# protoboard-63.net
KiCad netlist of a schematic drawn in EAGLE
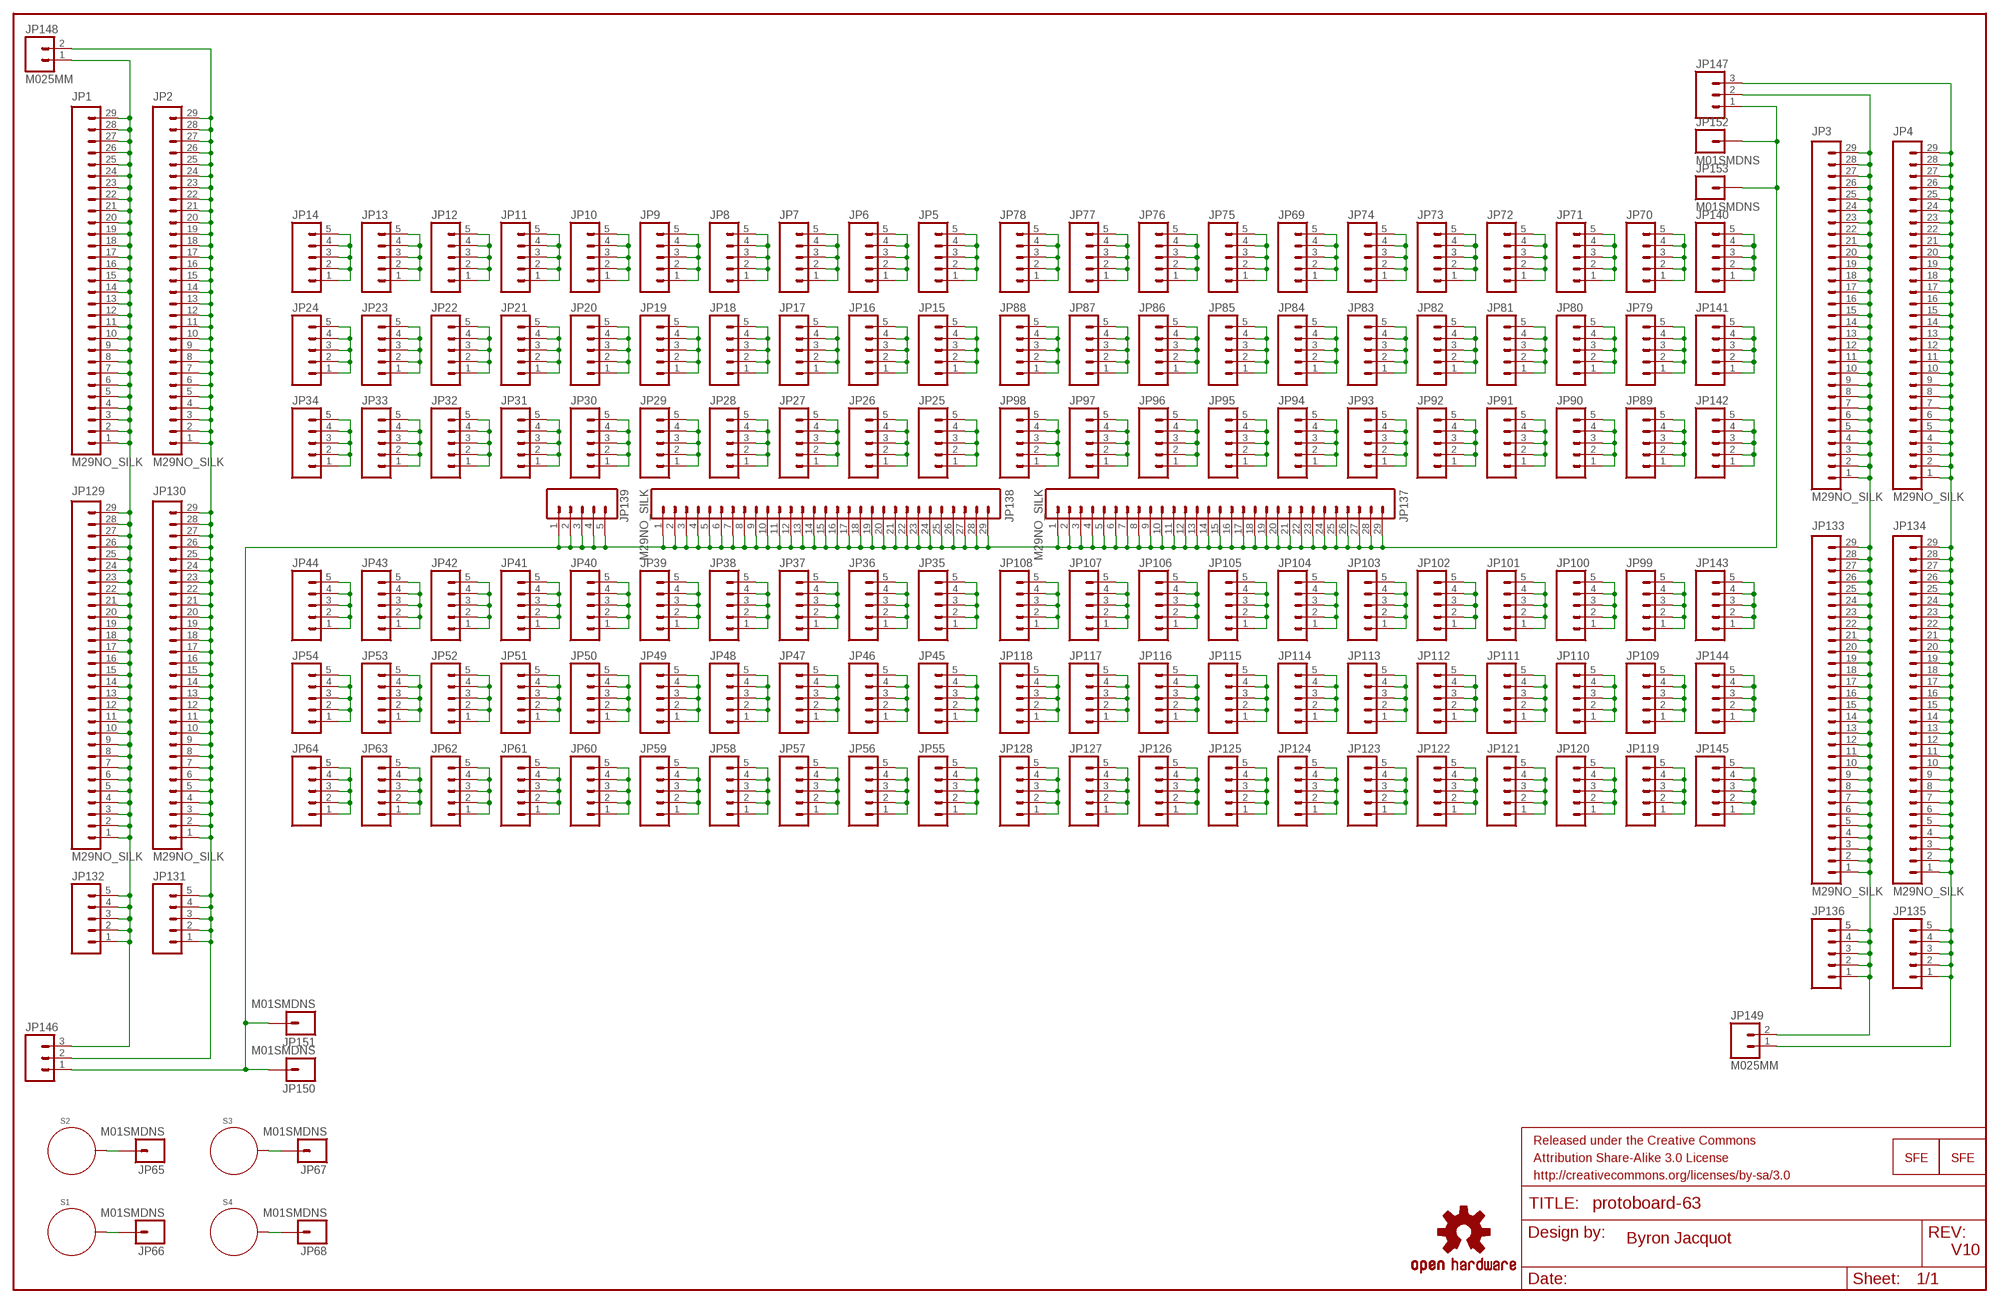
[diagram p0: schematic, sheet 1]

(export (version "E")
  (design (tool "Eeschema 10.0.6"))
  (components
    (comp (ref "FRAME2")
      (value "FRAME-LEDGER")
      (footprint "eagle-import:CREATIVE_COMMONS")
      (libsource (lib "eagle-import") (part "FRAME-LEDGER"))
    )
    (comp (ref "JP1")
      (value "M29NO_SILK")
      (footprint "eagle-import:1X29_NO_SILK")
      (libsource (lib "eagle-import") (part "M29NO_SILK"))
    )
    (comp (ref "JP2")
      (value "M29NO_SILK")
      (footprint "eagle-import:1X29_NO_SILK")
      (libsource (lib "eagle-import") (part "M29NO_SILK"))
    )
    (comp (ref "JP3")
      (value "M29NO_SILK")
      (footprint "eagle-import:1X29_NO_SILK")
      (libsource (lib "eagle-import") (part "M29NO_SILK"))
    )
    (comp (ref "JP4")
      (value "M29NO_SILK")
      (footprint "eagle-import:1X29_NO_SILK")
      (libsource (lib "eagle-import") (part "M29NO_SILK"))
    )
    (comp (ref "JP5")
      (value "M05NO_SILK")
      (footprint "eagle-import:1X05_NO_SILK")
      (libsource (lib "eagle-import") (part "M05NO_SILK"))
    )
    (comp (ref "JP6")
      (value "M05NO_SILK")
      (footprint "eagle-import:1X05_NO_SILK")
      (libsource (lib "eagle-import") (part "M05NO_SILK"))
    )
    (comp (ref "JP7")
      (value "M05NO_SILK")
      (footprint "eagle-import:1X05_NO_SILK")
      (libsource (lib "eagle-import") (part "M05NO_SILK"))
    )
    (comp (ref "JP8")
      (value "M05NO_SILK")
      (footprint "eagle-import:1X05_NO_SILK")
      (libsource (lib "eagle-import") (part "M05NO_SILK"))
    )
    (comp (ref "JP9")
      (value "M05NO_SILK")
      (footprint "eagle-import:1X05_NO_SILK")
      (libsource (lib "eagle-import") (part "M05NO_SILK"))
    )
    (comp (ref "JP10")
      (value "M05NO_SILK")
      (footprint "eagle-import:1X05_NO_SILK")
      (libsource (lib "eagle-import") (part "M05NO_SILK"))
    )
    (comp (ref "JP11")
      (value "M05NO_SILK")
      (footprint "eagle-import:1X05_NO_SILK")
      (libsource (lib "eagle-import") (part "M05NO_SILK"))
    )
    (comp (ref "JP12")
      (value "M05NO_SILK")
      (footprint "eagle-import:1X05_NO_SILK")
      (libsource (lib "eagle-import") (part "M05NO_SILK"))
    )
    (comp (ref "JP13")
      (value "M05NO_SILK")
      (footprint "eagle-import:1X05_NO_SILK")
      (libsource (lib "eagle-import") (part "M05NO_SILK"))
    )
    (comp (ref "JP14")
      (value "M05NO_SILK")
      (footprint "eagle-import:1X05_NO_SILK")
      (libsource (lib "eagle-import") (part "M05NO_SILK"))
    )
    (comp (ref "JP15")
      (value "M05NO_SILK")
      (footprint "eagle-import:1X05_NO_SILK")
      (libsource (lib "eagle-import") (part "M05NO_SILK"))
    )
    (comp (ref "JP16")
      (value "M05NO_SILK")
      (footprint "eagle-import:1X05_NO_SILK")
      (libsource (lib "eagle-import") (part "M05NO_SILK"))
    )
    (comp (ref "JP17")
      (value "M05NO_SILK")
      (footprint "eagle-import:1X05_NO_SILK")
      (libsource (lib "eagle-import") (part "M05NO_SILK"))
    )
    (comp (ref "JP18")
      (value "M05NO_SILK")
      (footprint "eagle-import:1X05_NO_SILK")
      (libsource (lib "eagle-import") (part "M05NO_SILK"))
    )
    (comp (ref "JP19")
      (value "M05NO_SILK")
      (footprint "eagle-import:1X05_NO_SILK")
      (libsource (lib "eagle-import") (part "M05NO_SILK"))
    )
    (comp (ref "JP20")
      (value "M05NO_SILK")
      (footprint "eagle-import:1X05_NO_SILK")
      (libsource (lib "eagle-import") (part "M05NO_SILK"))
    )
    (comp (ref "JP21")
      (value "M05NO_SILK")
      (footprint "eagle-import:1X05_NO_SILK")
      (libsource (lib "eagle-import") (part "M05NO_SILK"))
    )
    (comp (ref "JP22")
      (value "M05NO_SILK")
      (footprint "eagle-import:1X05_NO_SILK")
      (libsource (lib "eagle-import") (part "M05NO_SILK"))
    )
    (comp (ref "JP23")
      (value "M05NO_SILK")
      (footprint "eagle-import:1X05_NO_SILK")
      (libsource (lib "eagle-import") (part "M05NO_SILK"))
    )
    (comp (ref "JP24")
      (value "M05NO_SILK")
      (footprint "eagle-import:1X05_NO_SILK")
      (libsource (lib "eagle-import") (part "M05NO_SILK"))
    )
    (comp (ref "JP25")
      (value "M05NO_SILK")
      (footprint "eagle-import:1X05_NO_SILK")
      (libsource (lib "eagle-import") (part "M05NO_SILK"))
    )
    (comp (ref "JP26")
      (value "M05NO_SILK")
      (footprint "eagle-import:1X05_NO_SILK")
      (libsource (lib "eagle-import") (part "M05NO_SILK"))
    )
    (comp (ref "JP27")
      (value "M05NO_SILK")
      (footprint "eagle-import:1X05_NO_SILK")
      (libsource (lib "eagle-import") (part "M05NO_SILK"))
    )
    (comp (ref "JP28")
      (value "M05NO_SILK")
      (footprint "eagle-import:1X05_NO_SILK")
      (libsource (lib "eagle-import") (part "M05NO_SILK"))
    )
    (comp (ref "JP29")
      (value "M05NO_SILK")
      (footprint "eagle-import:1X05_NO_SILK")
      (libsource (lib "eagle-import") (part "M05NO_SILK"))
    )
    (comp (ref "JP30")
      (value "M05NO_SILK")
      (footprint "eagle-import:1X05_NO_SILK")
      (libsource (lib "eagle-import") (part "M05NO_SILK"))
    )
    (comp (ref "JP31")
      (value "M05NO_SILK")
      (footprint "eagle-import:1X05_NO_SILK")
      (libsource (lib "eagle-import") (part "M05NO_SILK"))
    )
    (comp (ref "JP32")
      (value "M05NO_SILK")
      (footprint "eagle-import:1X05_NO_SILK")
      (libsource (lib "eagle-import") (part "M05NO_SILK"))
    )
    (comp (ref "JP33")
      (value "M05NO_SILK")
      (footprint "eagle-import:1X05_NO_SILK")
      (libsource (lib "eagle-import") (part "M05NO_SILK"))
    )
    (comp (ref "JP34")
      (value "M05NO_SILK")
      (footprint "eagle-import:1X05_NO_SILK")
      (libsource (lib "eagle-import") (part "M05NO_SILK"))
    )
    (comp (ref "JP35")
      (value "M05NO_SILK")
      (footprint "eagle-import:1X05_NO_SILK")
      (libsource (lib "eagle-import") (part "M05NO_SILK"))
    )
    (comp (ref "JP36")
      (value "M05NO_SILK")
      (footprint "eagle-import:1X05_NO_SILK")
      (libsource (lib "eagle-import") (part "M05NO_SILK"))
    )
    (comp (ref "JP37")
      (value "M05NO_SILK")
      (footprint "eagle-import:1X05_NO_SILK")
      (libsource (lib "eagle-import") (part "M05NO_SILK"))
    )
    (comp (ref "JP38")
      (value "M05NO_SILK")
      (footprint "eagle-import:1X05_NO_SILK")
      (libsource (lib "eagle-import") (part "M05NO_SILK"))
    )
    (comp (ref "JP39")
      (value "M05NO_SILK")
      (footprint "eagle-import:1X05_NO_SILK")
      (libsource (lib "eagle-import") (part "M05NO_SILK"))
    )
    (comp (ref "JP40")
      (value "M05NO_SILK")
      (footprint "eagle-import:1X05_NO_SILK")
      (libsource (lib "eagle-import") (part "M05NO_SILK"))
    )
    (comp (ref "JP41")
      (value "M05NO_SILK")
      (footprint "eagle-import:1X05_NO_SILK")
      (libsource (lib "eagle-import") (part "M05NO_SILK"))
    )
    (comp (ref "JP42")
      (value "M05NO_SILK")
      (footprint "eagle-import:1X05_NO_SILK")
      (libsource (lib "eagle-import") (part "M05NO_SILK"))
    )
    (comp (ref "JP43")
      (value "M05NO_SILK")
      (footprint "eagle-import:1X05_NO_SILK")
      (libsource (lib "eagle-import") (part "M05NO_SILK"))
    )
    (comp (ref "JP44")
      (value "M05NO_SILK")
      (footprint "eagle-import:1X05_NO_SILK")
      (libsource (lib "eagle-import") (part "M05NO_SILK"))
    )
    (comp (ref "JP45")
      (value "M05NO_SILK")
      (footprint "eagle-import:1X05_NO_SILK")
      (libsource (lib "eagle-import") (part "M05NO_SILK"))
    )
    (comp (ref "JP46")
      (value "M05NO_SILK")
      (footprint "eagle-import:1X05_NO_SILK")
      (libsource (lib "eagle-import") (part "M05NO_SILK"))
    )
    (comp (ref "JP47")
      (value "M05NO_SILK")
      (footprint "eagle-import:1X05_NO_SILK")
      (libsource (lib "eagle-import") (part "M05NO_SILK"))
    )
    (comp (ref "JP48")
      (value "M05NO_SILK")
      (footprint "eagle-import:1X05_NO_SILK")
      (libsource (lib "eagle-import") (part "M05NO_SILK"))
    )
    (comp (ref "JP49")
      (value "M05NO_SILK")
      (footprint "eagle-import:1X05_NO_SILK")
      (libsource (lib "eagle-import") (part "M05NO_SILK"))
    )
    (comp (ref "JP50")
      (value "M05NO_SILK")
      (footprint "eagle-import:1X05_NO_SILK")
      (libsource (lib "eagle-import") (part "M05NO_SILK"))
    )
    (comp (ref "JP51")
      (value "M05NO_SILK")
      (footprint "eagle-import:1X05_NO_SILK")
      (libsource (lib "eagle-import") (part "M05NO_SILK"))
    )
    (comp (ref "JP52")
      (value "M05NO_SILK")
      (footprint "eagle-import:1X05_NO_SILK")
      (libsource (lib "eagle-import") (part "M05NO_SILK"))
    )
    (comp (ref "JP53")
      (value "M05NO_SILK")
      (footprint "eagle-import:1X05_NO_SILK")
      (libsource (lib "eagle-import") (part "M05NO_SILK"))
    )
    (comp (ref "JP54")
      (value "M05NO_SILK")
      (footprint "eagle-import:1X05_NO_SILK")
      (libsource (lib "eagle-import") (part "M05NO_SILK"))
    )
    (comp (ref "JP55")
      (value "M05NO_SILK")
      (footprint "eagle-import:1X05_NO_SILK")
      (libsource (lib "eagle-import") (part "M05NO_SILK"))
    )
    (comp (ref "JP56")
      (value "M05NO_SILK")
      (footprint "eagle-import:1X05_NO_SILK")
      (libsource (lib "eagle-import") (part "M05NO_SILK"))
    )
    (comp (ref "JP57")
      (value "M05NO_SILK")
      (footprint "eagle-import:1X05_NO_SILK")
      (libsource (lib "eagle-import") (part "M05NO_SILK"))
    )
    (comp (ref "JP58")
      (value "M05NO_SILK")
      (footprint "eagle-import:1X05_NO_SILK")
      (libsource (lib "eagle-import") (part "M05NO_SILK"))
    )
    (comp (ref "JP59")
      (value "M05NO_SILK")
      (footprint "eagle-import:1X05_NO_SILK")
      (libsource (lib "eagle-import") (part "M05NO_SILK"))
    )
    (comp (ref "JP60")
      (value "M05NO_SILK")
      (footprint "eagle-import:1X05_NO_SILK")
      (libsource (lib "eagle-import") (part "M05NO_SILK"))
    )
    (comp (ref "JP61")
      (value "M05NO_SILK")
      (footprint "eagle-import:1X05_NO_SILK")
      (libsource (lib "eagle-import") (part "M05NO_SILK"))
    )
    (comp (ref "JP62")
      (value "M05NO_SILK")
      (footprint "eagle-import:1X05_NO_SILK")
      (libsource (lib "eagle-import") (part "M05NO_SILK"))
    )
    (comp (ref "JP63")
      (value "M05NO_SILK")
      (footprint "eagle-import:1X05_NO_SILK")
      (libsource (lib "eagle-import") (part "M05NO_SILK"))
    )
    (comp (ref "JP64")
      (value "M05NO_SILK")
      (footprint "eagle-import:1X05_NO_SILK")
      (libsource (lib "eagle-import") (part "M05NO_SILK"))
    )
    (comp (ref "JP65")
      (value "M01SMDNS")
      (footprint "eagle-import:1X01NS")
      (libsource (lib "eagle-import") (part "M01SMDNS"))
    )
    (comp (ref "JP66")
      (value "M01SMDNS")
      (footprint "eagle-import:1X01NS")
      (libsource (lib "eagle-import") (part "M01SMDNS"))
    )
    (comp (ref "JP67")
      (value "M01SMDNS")
      (footprint "eagle-import:1X01NS")
      (libsource (lib "eagle-import") (part "M01SMDNS"))
    )
    (comp (ref "JP68")
      (value "M01SMDNS")
      (footprint "eagle-import:1X01NS")
      (libsource (lib "eagle-import") (part "M01SMDNS"))
    )
    (comp (ref "JP69")
      (value "M05NO_SILK")
      (footprint "eagle-import:1X05_NO_SILK")
      (libsource (lib "eagle-import") (part "M05NO_SILK"))
    )
    (comp (ref "JP70")
      (value "M05NO_SILK")
      (footprint "eagle-import:1X05_NO_SILK")
      (libsource (lib "eagle-import") (part "M05NO_SILK"))
    )
    (comp (ref "JP71")
      (value "M05NO_SILK")
      (footprint "eagle-import:1X05_NO_SILK")
      (libsource (lib "eagle-import") (part "M05NO_SILK"))
    )
    (comp (ref "JP72")
      (value "M05NO_SILK")
      (footprint "eagle-import:1X05_NO_SILK")
      (libsource (lib "eagle-import") (part "M05NO_SILK"))
    )
    (comp (ref "JP73")
      (value "M05NO_SILK")
      (footprint "eagle-import:1X05_NO_SILK")
      (libsource (lib "eagle-import") (part "M05NO_SILK"))
    )
    (comp (ref "JP74")
      (value "M05NO_SILK")
      (footprint "eagle-import:1X05_NO_SILK")
      (libsource (lib "eagle-import") (part "M05NO_SILK"))
    )
    (comp (ref "JP75")
      (value "M05NO_SILK")
      (footprint "eagle-import:1X05_NO_SILK")
      (libsource (lib "eagle-import") (part "M05NO_SILK"))
    )
    (comp (ref "JP76")
      (value "M05NO_SILK")
      (footprint "eagle-import:1X05_NO_SILK")
      (libsource (lib "eagle-import") (part "M05NO_SILK"))
    )
    (comp (ref "JP77")
      (value "M05NO_SILK")
      (footprint "eagle-import:1X05_NO_SILK")
      (libsource (lib "eagle-import") (part "M05NO_SILK"))
    )
    (comp (ref "JP78")
      (value "M05NO_SILK")
      (footprint "eagle-import:1X05_NO_SILK")
      (libsource (lib "eagle-import") (part "M05NO_SILK"))
    )
    (comp (ref "JP79")
      (value "M05NO_SILK")
      (footprint "eagle-import:1X05_NO_SILK")
      (libsource (lib "eagle-import") (part "M05NO_SILK"))
    )
    (comp (ref "JP80")
      (value "M05NO_SILK")
      (footprint "eagle-import:1X05_NO_SILK")
      (libsource (lib "eagle-import") (part "M05NO_SILK"))
    )
    (comp (ref "JP81")
      (value "M05NO_SILK")
      (footprint "eagle-import:1X05_NO_SILK")
      (libsource (lib "eagle-import") (part "M05NO_SILK"))
    )
    (comp (ref "JP82")
      (value "M05NO_SILK")
      (footprint "eagle-import:1X05_NO_SILK")
      (libsource (lib "eagle-import") (part "M05NO_SILK"))
    )
    (comp (ref "JP83")
      (value "M05NO_SILK")
      (footprint "eagle-import:1X05_NO_SILK")
      (libsource (lib "eagle-import") (part "M05NO_SILK"))
    )
    (comp (ref "JP84")
      (value "M05NO_SILK")
      (footprint "eagle-import:1X05_NO_SILK")
      (libsource (lib "eagle-import") (part "M05NO_SILK"))
    )
    (comp (ref "JP85")
      (value "M05NO_SILK")
      (footprint "eagle-import:1X05_NO_SILK")
      (libsource (lib "eagle-import") (part "M05NO_SILK"))
    )
    (comp (ref "JP86")
      (value "M05NO_SILK")
      (footprint "eagle-import:1X05_NO_SILK")
      (libsource (lib "eagle-import") (part "M05NO_SILK"))
    )
    (comp (ref "JP87")
      (value "M05NO_SILK")
      (footprint "eagle-import:1X05_NO_SILK")
      (libsource (lib "eagle-import") (part "M05NO_SILK"))
    )
    (comp (ref "JP88")
      (value "M05NO_SILK")
      (footprint "eagle-import:1X05_NO_SILK")
      (libsource (lib "eagle-import") (part "M05NO_SILK"))
    )
    (comp (ref "JP89")
      (value "M05NO_SILK")
      (footprint "eagle-import:1X05_NO_SILK")
      (libsource (lib "eagle-import") (part "M05NO_SILK"))
    )
    (comp (ref "JP90")
      (value "M05NO_SILK")
      (footprint "eagle-import:1X05_NO_SILK")
      (libsource (lib "eagle-import") (part "M05NO_SILK"))
    )
    (comp (ref "JP91")
      (value "M05NO_SILK")
      (footprint "eagle-import:1X05_NO_SILK")
      (libsource (lib "eagle-import") (part "M05NO_SILK"))
    )
    (comp (ref "JP92")
      (value "M05NO_SILK")
      (footprint "eagle-import:1X05_NO_SILK")
      (libsource (lib "eagle-import") (part "M05NO_SILK"))
    )
    (comp (ref "JP93")
      (value "M05NO_SILK")
      (footprint "eagle-import:1X05_NO_SILK")
      (libsource (lib "eagle-import") (part "M05NO_SILK"))
    )
    (comp (ref "JP94")
      (value "M05NO_SILK")
      (footprint "eagle-import:1X05_NO_SILK")
      (libsource (lib "eagle-import") (part "M05NO_SILK"))
    )
    (comp (ref "JP95")
      (value "M05NO_SILK")
      (footprint "eagle-import:1X05_NO_SILK")
      (libsource (lib "eagle-import") (part "M05NO_SILK"))
    )
    (comp (ref "JP96")
      (value "M05NO_SILK")
      (footprint "eagle-import:1X05_NO_SILK")
      (libsource (lib "eagle-import") (part "M05NO_SILK"))
    )
    (comp (ref "JP97")
      (value "M05NO_SILK")
      (footprint "eagle-import:1X05_NO_SILK")
      (libsource (lib "eagle-import") (part "M05NO_SILK"))
    )
    (comp (ref "JP98")
      (value "M05NO_SILK")
      (footprint "eagle-import:1X05_NO_SILK")
      (libsource (lib "eagle-import") (part "M05NO_SILK"))
    )
    (comp (ref "JP99")
      (value "M05NO_SILK")
      (footprint "eagle-import:1X05_NO_SILK")
      (libsource (lib "eagle-import") (part "M05NO_SILK"))
    )
    (comp (ref "JP100")
      (value "M05NO_SILK")
      (footprint "eagle-import:1X05_NO_SILK")
      (libsource (lib "eagle-import") (part "M05NO_SILK"))
    )
    (comp (ref "JP101")
      (value "M05NO_SILK")
      (footprint "eagle-import:1X05_NO_SILK")
      (libsource (lib "eagle-import") (part "M05NO_SILK"))
    )
    (comp (ref "JP102")
      (value "M05NO_SILK")
      (footprint "eagle-import:1X05_NO_SILK")
      (libsource (lib "eagle-import") (part "M05NO_SILK"))
    )
    (comp (ref "JP103")
      (value "M05NO_SILK")
      (footprint "eagle-import:1X05_NO_SILK")
      (libsource (lib "eagle-import") (part "M05NO_SILK"))
    )
    (comp (ref "JP104")
      (value "M05NO_SILK")
      (footprint "eagle-import:1X05_NO_SILK")
      (libsource (lib "eagle-import") (part "M05NO_SILK"))
    )
    (comp (ref "JP105")
      (value "M05NO_SILK")
      (footprint "eagle-import:1X05_NO_SILK")
      (libsource (lib "eagle-import") (part "M05NO_SILK"))
    )
    (comp (ref "JP106")
      (value "M05NO_SILK")
      (footprint "eagle-import:1X05_NO_SILK")
      (libsource (lib "eagle-import") (part "M05NO_SILK"))
    )
    (comp (ref "JP107")
      (value "M05NO_SILK")
      (footprint "eagle-import:1X05_NO_SILK")
      (libsource (lib "eagle-import") (part "M05NO_SILK"))
    )
    (comp (ref "JP108")
      (value "M05NO_SILK")
      (footprint "eagle-import:1X05_NO_SILK")
      (libsource (lib "eagle-import") (part "M05NO_SILK"))
    )
    (comp (ref "JP109")
      (value "M05NO_SILK")
      (footprint "eagle-import:1X05_NO_SILK")
      (libsource (lib "eagle-import") (part "M05NO_SILK"))
    )
    (comp (ref "JP110")
      (value "M05NO_SILK")
      (footprint "eagle-import:1X05_NO_SILK")
      (libsource (lib "eagle-import") (part "M05NO_SILK"))
    )
    (comp (ref "JP111")
      (value "M05NO_SILK")
      (footprint "eagle-import:1X05_NO_SILK")
      (libsource (lib "eagle-import") (part "M05NO_SILK"))
    )
    (comp (ref "JP112")
      (value "M05NO_SILK")
      (footprint "eagle-import:1X05_NO_SILK")
      (libsource (lib "eagle-import") (part "M05NO_SILK"))
    )
    (comp (ref "JP113")
      (value "M05NO_SILK")
      (footprint "eagle-import:1X05_NO_SILK")
      (libsource (lib "eagle-import") (part "M05NO_SILK"))
    )
    (comp (ref "JP114")
      (value "M05NO_SILK")
      (footprint "eagle-import:1X05_NO_SILK")
      (libsource (lib "eagle-import") (part "M05NO_SILK"))
    )
    (comp (ref "JP115")
      (value "M05NO_SILK")
      (footprint "eagle-import:1X05_NO_SILK")
      (libsource (lib "eagle-import") (part "M05NO_SILK"))
    )
    (comp (ref "JP116")
      (value "M05NO_SILK")
      (footprint "eagle-import:1X05_NO_SILK")
      (libsource (lib "eagle-import") (part "M05NO_SILK"))
    )
    (comp (ref "JP117")
      (value "M05NO_SILK")
      (footprint "eagle-import:1X05_NO_SILK")
      (libsource (lib "eagle-import") (part "M05NO_SILK"))
    )
    (comp (ref "JP118")
      (value "M05NO_SILK")
      (footprint "eagle-import:1X05_NO_SILK")
      (libsource (lib "eagle-import") (part "M05NO_SILK"))
    )
    (comp (ref "JP119")
      (value "M05NO_SILK")
      (footprint "eagle-import:1X05_NO_SILK")
      (libsource (lib "eagle-import") (part "M05NO_SILK"))
    )
    (comp (ref "JP120")
      (value "M05NO_SILK")
      (footprint "eagle-import:1X05_NO_SILK")
      (libsource (lib "eagle-import") (part "M05NO_SILK"))
    )
    (comp (ref "JP121")
      (value "M05NO_SILK")
      (footprint "eagle-import:1X05_NO_SILK")
      (libsource (lib "eagle-import") (part "M05NO_SILK"))
    )
    (comp (ref "JP122")
      (value "M05NO_SILK")
      (footprint "eagle-import:1X05_NO_SILK")
      (libsource (lib "eagle-import") (part "M05NO_SILK"))
    )
    (comp (ref "JP123")
      (value "M05NO_SILK")
      (footprint "eagle-import:1X05_NO_SILK")
      (libsource (lib "eagle-import") (part "M05NO_SILK"))
    )
    (comp (ref "JP124")
      (value "M05NO_SILK")
      (footprint "eagle-import:1X05_NO_SILK")
      (libsource (lib "eagle-import") (part "M05NO_SILK"))
    )
    (comp (ref "JP125")
      (value "M05NO_SILK")
      (footprint "eagle-import:1X05_NO_SILK")
      (libsource (lib "eagle-import") (part "M05NO_SILK"))
    )
    (comp (ref "JP126")
      (value "M05NO_SILK")
      (footprint "eagle-import:1X05_NO_SILK")
      (libsource (lib "eagle-import") (part "M05NO_SILK"))
    )
    (comp (ref "JP127")
      (value "M05NO_SILK")
      (footprint "eagle-import:1X05_NO_SILK")
      (libsource (lib "eagle-import") (part "M05NO_SILK"))
    )
    (comp (ref "JP128")
      (value "M05NO_SILK")
      (footprint "eagle-import:1X05_NO_SILK")
      (libsource (lib "eagle-import") (part "M05NO_SILK"))
    )
    (comp (ref "JP129")
      (value "M29NO_SILK")
      (footprint "eagle-import:1X29_NO_SILK")
      (libsource (lib "eagle-import") (part "M29NO_SILK"))
    )
    (comp (ref "JP130")
      (value "M29NO_SILK")
      (footprint "eagle-import:1X29_NO_SILK")
      (libsource (lib "eagle-import") (part "M29NO_SILK"))
    )
    (comp (ref "JP131")
      (value "M05NO_SILK")
      (footprint "eagle-import:1X05_NO_SILK")
      (libsource (lib "eagle-import") (part "M05NO_SILK"))
    )
    (comp (ref "JP132")
      (value "M05NO_SILK")
      (footprint "eagle-import:1X05_NO_SILK")
      (libsource (lib "eagle-import") (part "M05NO_SILK"))
    )
    (comp (ref "JP133")
      (value "M29NO_SILK")
      (footprint "eagle-import:1X29_NO_SILK")
      (libsource (lib "eagle-import") (part "M29NO_SILK"))
    )
    (comp (ref "JP134")
      (value "M29NO_SILK")
      (footprint "eagle-import:1X29_NO_SILK")
      (libsource (lib "eagle-import") (part "M29NO_SILK"))
    )
    (comp (ref "JP135")
      (value "M05NO_SILK")
      (footprint "eagle-import:1X05_NO_SILK")
      (libsource (lib "eagle-import") (part "M05NO_SILK"))
    )
    (comp (ref "JP136")
      (value "M05NO_SILK")
      (footprint "eagle-import:1X05_NO_SILK")
      (libsource (lib "eagle-import") (part "M05NO_SILK"))
    )
    (comp (ref "JP137")
      (value "M29NO_SILK")
      (footprint "eagle-import:1X29_NO_SILK")
      (libsource (lib "eagle-import") (part "M29NO_SILK"))
    )
    (comp (ref "JP138")
      (value "M29NO_SILK")
      (footprint "eagle-import:1X29_NO_SILK")
      (libsource (lib "eagle-import") (part "M29NO_SILK"))
    )
    (comp (ref "JP139")
      (value "M05NO_SILK")
      (footprint "eagle-import:1X05_NO_SILK")
      (libsource (lib "eagle-import") (part "M05NO_SILK"))
    )
    (comp (ref "JP140")
      (value "M05NO_SILK")
      (footprint "eagle-import:1X05_NO_SILK")
      (libsource (lib "eagle-import") (part "M05NO_SILK"))
    )
    (comp (ref "JP141")
      (value "M05NO_SILK")
      (footprint "eagle-import:1X05_NO_SILK")
      (libsource (lib "eagle-import") (part "M05NO_SILK"))
    )
    (comp (ref "JP142")
      (value "M05NO_SILK")
      (footprint "eagle-import:1X05_NO_SILK")
      (libsource (lib "eagle-import") (part "M05NO_SILK"))
    )
    (comp (ref "JP143")
      (value "M05NO_SILK")
      (footprint "eagle-import:1X05_NO_SILK")
      (libsource (lib "eagle-import") (part "M05NO_SILK"))
    )
    (comp (ref "JP144")
      (value "M05NO_SILK")
      (footprint "eagle-import:1X05_NO_SILK")
      (libsource (lib "eagle-import") (part "M05NO_SILK"))
    )
    (comp (ref "JP145")
      (value "M05NO_SILK")
      (footprint "eagle-import:1X05_NO_SILK")
      (libsource (lib "eagle-import") (part "M05NO_SILK"))
    )
    (comp (ref "JP146")
      (value "M03-SCREW-5MM")
      (footprint "eagle-import:SCREWTERMINAL-5MM-3")
      (libsource (lib "eagle-import") (part "M03-SCREW-5MM"))
    )
    (comp (ref "JP147")
      (value "M03-SCREW-5MM")
      (footprint "eagle-import:SCREWTERMINAL-5MM-3")
      (libsource (lib "eagle-import") (part "M03-SCREW-5MM"))
    )
    (comp (ref "JP148")
      (value "M025MM")
      (footprint "eagle-import:SCREWTERMINAL-5MM-2")
      (libsource (lib "eagle-import") (part "M025MM"))
    )
    (comp (ref "JP149")
      (value "M025MM")
      (footprint "eagle-import:SCREWTERMINAL-5MM-2")
      (libsource (lib "eagle-import") (part "M025MM"))
    )
    (comp (ref "JP150")
      (value "M01SMDNS")
      (footprint "eagle-import:1X01NS")
      (libsource (lib "eagle-import") (part "M01SMDNS"))
    )
    (comp (ref "JP151")
      (value "M01SMDNS")
      (footprint "eagle-import:1X01NS")
      (libsource (lib "eagle-import") (part "M01SMDNS"))
    )
    (comp (ref "JP152")
      (value "M01SMDNS")
      (footprint "eagle-import:1X01NS")
      (libsource (lib "eagle-import") (part "M01SMDNS"))
    )
    (comp (ref "JP153")
      (value "M01SMDNS")
      (footprint "eagle-import:1X01NS")
      (libsource (lib "eagle-import") (part "M01SMDNS"))
    )
    (comp (ref "LOGO1")
      (value "LOGO-SFENEW")
      (footprint "eagle-import:SFE-NEW-WEBLOGO")
      (libsource (lib "eagle-import") (part "LOGO-SFENEW"))
    )
    (comp (ref "LOGO2")
      (value "LOGO-SFENEW")
      (footprint "eagle-import:SFE-NEW-WEBLOGO")
      (libsource (lib "eagle-import") (part "LOGO-SFENEW"))
    )
    (comp (ref "LOGO3")
      (value "OSHW-LOGOS")
      (footprint "eagle-import:OSHW-LOGO-S")
      (libsource (lib "eagle-import") (part "OSHW-LOGOS"))
    )
    (comp (ref "S1")
      (value "STANDOFF_ELECTRICAL")
      (footprint "eagle-import:STANDOFF-ELECTRICAL")
      (libsource (lib "eagle-import") (part "STANDOFF_ELECTRICAL"))
    )
    (comp (ref "S2")
      (value "STANDOFF_ELECTRICAL")
      (footprint "eagle-import:STANDOFF-ELECTRICAL")
      (libsource (lib "eagle-import") (part "STANDOFF_ELECTRICAL"))
    )
    (comp (ref "S3")
      (value "STANDOFF_ELECTRICAL")
      (footprint "eagle-import:STANDOFF-ELECTRICAL")
      (libsource (lib "eagle-import") (part "STANDOFF_ELECTRICAL"))
    )
    (comp (ref "S4")
      (value "STANDOFF_ELECTRICAL")
      (footprint "eagle-import:STANDOFF-ELECTRICAL")
      (libsource (lib "eagle-import") (part "STANDOFF_ELECTRICAL"))
    )
  )
  (nets
    (net (code "1") (name "Net-(JP1-Pad1)") (class "Default")
      (node (ref "JP1") (pin "1") (pinfunction "1_1") (pintype "passive"))
      (node (ref "JP1") (pin "10") (pinfunction "10_10") (pintype "passive"))
      (node (ref "JP1") (pin "11") (pinfunction "11_11") (pintype "passive"))
      (node (ref "JP1") (pin "12") (pinfunction "12_12") (pintype "passive"))
      (node (ref "JP1") (pin "13") (pinfunction "13_13") (pintype "passive"))
      (node (ref "JP1") (pin "14") (pinfunction "14_14") (pintype "passive"))
      (node (ref "JP1") (pin "15") (pinfunction "15_15") (pintype "passive"))
      (node (ref "JP1") (pin "16") (pinfunction "16_16") (pintype "passive"))
      (node (ref "JP1") (pin "17") (pinfunction "17_17") (pintype "passive"))
      (node (ref "JP1") (pin "18") (pinfunction "18_18") (pintype "passive"))
      (node (ref "JP1") (pin "19") (pinfunction "19_19") (pintype "passive"))
      (node (ref "JP1") (pin "2") (pinfunction "2_2") (pintype "passive"))
      (node (ref "JP1") (pin "20") (pinfunction "20_20") (pintype "passive"))
      (node (ref "JP1") (pin "21") (pinfunction "21_21") (pintype "passive"))
      (node (ref "JP1") (pin "22") (pinfunction "22_22") (pintype "passive"))
      (node (ref "JP1") (pin "23") (pinfunction "23_23") (pintype "passive"))
      (node (ref "JP1") (pin "24") (pinfunction "24_24") (pintype "passive"))
      (node (ref "JP1") (pin "25") (pinfunction "25_25") (pintype "passive"))
      (node (ref "JP1") (pin "26") (pinfunction "26_26") (pintype "passive"))
      (node (ref "JP1") (pin "27") (pinfunction "27_27") (pintype "passive"))
      (node (ref "JP1") (pin "28") (pinfunction "28_28") (pintype "passive"))
      (node (ref "JP1") (pin "29") (pinfunction "29_29") (pintype "passive"))
      (node (ref "JP1") (pin "3") (pinfunction "3_3") (pintype "passive"))
      (node (ref "JP1") (pin "4") (pinfunction "4_4") (pintype "passive"))
      (node (ref "JP1") (pin "5") (pinfunction "5_5") (pintype "passive"))
      (node (ref "JP1") (pin "6") (pinfunction "6_6") (pintype "passive"))
      (node (ref "JP1") (pin "7") (pinfunction "7_7") (pintype "passive"))
      (node (ref "JP1") (pin "8") (pinfunction "8_8") (pintype "passive"))
      (node (ref "JP1") (pin "9") (pinfunction "9_9") (pintype "passive"))
      (node (ref "JP129") (pin "1") (pinfunction "1_1") (pintype "passive"))
      (node (ref "JP129") (pin "10") (pinfunction "10_10") (pintype "passive"))
      (node (ref "JP129") (pin "11") (pinfunction "11_11") (pintype "passive"))
      (node (ref "JP129") (pin "12") (pinfunction "12_12") (pintype "passive"))
      (node (ref "JP129") (pin "13") (pinfunction "13_13") (pintype "passive"))
      (node (ref "JP129") (pin "14") (pinfunction "14_14") (pintype "passive"))
      (node (ref "JP129") (pin "15") (pinfunction "15_15") (pintype "passive"))
      (node (ref "JP129") (pin "16") (pinfunction "16_16") (pintype "passive"))
      (node (ref "JP129") (pin "17") (pinfunction "17_17") (pintype "passive"))
      (node (ref "JP129") (pin "18") (pinfunction "18_18") (pintype "passive"))
      (node (ref "JP129") (pin "19") (pinfunction "19_19") (pintype "passive"))
      (node (ref "JP129") (pin "2") (pinfunction "2_2") (pintype "passive"))
      (node (ref "JP129") (pin "20") (pinfunction "20_20") (pintype "passive"))
      (node (ref "JP129") (pin "21") (pinfunction "21_21") (pintype "passive"))
      (node (ref "JP129") (pin "22") (pinfunction "22_22") (pintype "passive"))
      (node (ref "JP129") (pin "23") (pinfunction "23_23") (pintype "passive"))
      (node (ref "JP129") (pin "24") (pinfunction "24_24") (pintype "passive"))
      (node (ref "JP129") (pin "25") (pinfunction "25_25") (pintype "passive"))
      (node (ref "JP129") (pin "26") (pinfunction "26_26") (pintype "passive"))
      (node (ref "JP129") (pin "27") (pinfunction "27_27") (pintype "passive"))
      (node (ref "JP129") (pin "28") (pinfunction "28_28") (pintype "passive"))
      (node (ref "JP129") (pin "29") (pinfunction "29_29") (pintype "passive"))
      (node (ref "JP129") (pin "3") (pinfunction "3_3") (pintype "passive"))
      (node (ref "JP129") (pin "4") (pinfunction "4_4") (pintype "passive"))
      (node (ref "JP129") (pin "5") (pinfunction "5_5") (pintype "passive"))
      (node (ref "JP129") (pin "6") (pinfunction "6_6") (pintype "passive"))
      (node (ref "JP129") (pin "7") (pinfunction "7_7") (pintype "passive"))
      (node (ref "JP129") (pin "8") (pinfunction "8_8") (pintype "passive"))
      (node (ref "JP129") (pin "9") (pinfunction "9_9") (pintype "passive"))
      (node (ref "JP132") (pin "1") (pinfunction "1_1") (pintype "passive"))
      (node (ref "JP132") (pin "2") (pinfunction "2_2") (pintype "passive"))
      (node (ref "JP132") (pin "3") (pinfunction "3_3") (pintype "passive"))
      (node (ref "JP132") (pin "4") (pinfunction "4_4") (pintype "passive"))
      (node (ref "JP132") (pin "5") (pinfunction "5_5") (pintype "passive"))
      (node (ref "JP146") (pin "3") (pinfunction "3_3") (pintype "passive"))
      (node (ref "JP148") (pin "1") (pinfunction "1_1") (pintype "passive"))
    )
    (net (code "2") (name "Net-(JP5-Pad1)") (class "Default")
      (node (ref "JP5") (pin "1") (pinfunction "1_1") (pintype "passive"))
      (node (ref "JP5") (pin "2") (pinfunction "2_2") (pintype "passive"))
      (node (ref "JP5") (pin "3") (pinfunction "3_3") (pintype "passive"))
      (node (ref "JP5") (pin "4") (pinfunction "4_4") (pintype "passive"))
      (node (ref "JP5") (pin "5") (pinfunction "5_5") (pintype "passive"))
    )
    (net (code "3") (name "Net-(JP6-Pad1)") (class "Default")
      (node (ref "JP6") (pin "1") (pinfunction "1_1") (pintype "passive"))
      (node (ref "JP6") (pin "2") (pinfunction "2_2") (pintype "passive"))
      (node (ref "JP6") (pin "3") (pinfunction "3_3") (pintype "passive"))
      (node (ref "JP6") (pin "4") (pinfunction "4_4") (pintype "passive"))
      (node (ref "JP6") (pin "5") (pinfunction "5_5") (pintype "passive"))
    )
    (net (code "4") (name "Net-(JP7-Pad1)") (class "Default")
      (node (ref "JP7") (pin "1") (pinfunction "1_1") (pintype "passive"))
      (node (ref "JP7") (pin "2") (pinfunction "2_2") (pintype "passive"))
      (node (ref "JP7") (pin "3") (pinfunction "3_3") (pintype "passive"))
      (node (ref "JP7") (pin "4") (pinfunction "4_4") (pintype "passive"))
      (node (ref "JP7") (pin "5") (pinfunction "5_5") (pintype "passive"))
    )
    (net (code "5") (name "Net-(JP8-Pad1)") (class "Default")
      (node (ref "JP8") (pin "1") (pinfunction "1_1") (pintype "passive"))
      (node (ref "JP8") (pin "2") (pinfunction "2_2") (pintype "passive"))
      (node (ref "JP8") (pin "3") (pinfunction "3_3") (pintype "passive"))
      (node (ref "JP8") (pin "4") (pinfunction "4_4") (pintype "passive"))
      (node (ref "JP8") (pin "5") (pinfunction "5_5") (pintype "passive"))
    )
    (net (code "6") (name "Net-(JP9-Pad1)") (class "Default")
      (node (ref "JP9") (pin "1") (pinfunction "1_1") (pintype "passive"))
      (node (ref "JP9") (pin "2") (pinfunction "2_2") (pintype "passive"))
      (node (ref "JP9") (pin "3") (pinfunction "3_3") (pintype "passive"))
      (node (ref "JP9") (pin "4") (pinfunction "4_4") (pintype "passive"))
      (node (ref "JP9") (pin "5") (pinfunction "5_5") (pintype "passive"))
    )
    (net (code "7") (name "Net-(JP10-Pad1)") (class "Default")
      (node (ref "JP10") (pin "1") (pinfunction "1_1") (pintype "passive"))
      (node (ref "JP10") (pin "2") (pinfunction "2_2") (pintype "passive"))
      (node (ref "JP10") (pin "3") (pinfunction "3_3") (pintype "passive"))
      (node (ref "JP10") (pin "4") (pinfunction "4_4") (pintype "passive"))
      (node (ref "JP10") (pin "5") (pinfunction "5_5") (pintype "passive"))
    )
    (net (code "8") (name "Net-(JP11-Pad1)") (class "Default")
      (node (ref "JP11") (pin "1") (pinfunction "1_1") (pintype "passive"))
      (node (ref "JP11") (pin "2") (pinfunction "2_2") (pintype "passive"))
      (node (ref "JP11") (pin "3") (pinfunction "3_3") (pintype "passive"))
      (node (ref "JP11") (pin "4") (pinfunction "4_4") (pintype "passive"))
      (node (ref "JP11") (pin "5") (pinfunction "5_5") (pintype "passive"))
    )
    (net (code "9") (name "Net-(JP12-Pad1)") (class "Default")
      (node (ref "JP12") (pin "1") (pinfunction "1_1") (pintype "passive"))
      (node (ref "JP12") (pin "2") (pinfunction "2_2") (pintype "passive"))
      (node (ref "JP12") (pin "3") (pinfunction "3_3") (pintype "passive"))
      (node (ref "JP12") (pin "4") (pinfunction "4_4") (pintype "passive"))
      (node (ref "JP12") (pin "5") (pinfunction "5_5") (pintype "passive"))
    )
    (net (code "10") (name "Net-(JP13-Pad1)") (class "Default")
      (node (ref "JP13") (pin "1") (pinfunction "1_1") (pintype "passive"))
      (node (ref "JP13") (pin "2") (pinfunction "2_2") (pintype "passive"))
      (node (ref "JP13") (pin "3") (pinfunction "3_3") (pintype "passive"))
      (node (ref "JP13") (pin "4") (pinfunction "4_4") (pintype "passive"))
      (node (ref "JP13") (pin "5") (pinfunction "5_5") (pintype "passive"))
    )
    (net (code "11") (name "Net-(JP14-Pad1)") (class "Default")
      (node (ref "JP14") (pin "1") (pinfunction "1_1") (pintype "passive"))
      (node (ref "JP14") (pin "2") (pinfunction "2_2") (pintype "passive"))
      (node (ref "JP14") (pin "3") (pinfunction "3_3") (pintype "passive"))
      (node (ref "JP14") (pin "4") (pinfunction "4_4") (pintype "passive"))
      (node (ref "JP14") (pin "5") (pinfunction "5_5") (pintype "passive"))
    )
    (net (code "12") (name "Net-(JP15-Pad1)") (class "Default")
      (node (ref "JP15") (pin "1") (pinfunction "1_1") (pintype "passive"))
      (node (ref "JP15") (pin "2") (pinfunction "2_2") (pintype "passive"))
      (node (ref "JP15") (pin "3") (pinfunction "3_3") (pintype "passive"))
      (node (ref "JP15") (pin "4") (pinfunction "4_4") (pintype "passive"))
      (node (ref "JP15") (pin "5") (pinfunction "5_5") (pintype "passive"))
    )
    (net (code "13") (name "Net-(JP16-Pad1)") (class "Default")
      (node (ref "JP16") (pin "1") (pinfunction "1_1") (pintype "passive"))
      (node (ref "JP16") (pin "2") (pinfunction "2_2") (pintype "passive"))
      (node (ref "JP16") (pin "3") (pinfunction "3_3") (pintype "passive"))
      (node (ref "JP16") (pin "4") (pinfunction "4_4") (pintype "passive"))
      (node (ref "JP16") (pin "5") (pinfunction "5_5") (pintype "passive"))
    )
    (net (code "14") (name "Net-(JP17-Pad1)") (class "Default")
      (node (ref "JP17") (pin "1") (pinfunction "1_1") (pintype "passive"))
      (node (ref "JP17") (pin "2") (pinfunction "2_2") (pintype "passive"))
      (node (ref "JP17") (pin "3") (pinfunction "3_3") (pintype "passive"))
      (node (ref "JP17") (pin "4") (pinfunction "4_4") (pintype "passive"))
      (node (ref "JP17") (pin "5") (pinfunction "5_5") (pintype "passive"))
    )
    (net (code "15") (name "Net-(JP18-Pad1)") (class "Default")
      (node (ref "JP18") (pin "1") (pinfunction "1_1") (pintype "passive"))
      (node (ref "JP18") (pin "2") (pinfunction "2_2") (pintype "passive"))
      (node (ref "JP18") (pin "3") (pinfunction "3_3") (pintype "passive"))
      (node (ref "JP18") (pin "4") (pinfunction "4_4") (pintype "passive"))
      (node (ref "JP18") (pin "5") (pinfunction "5_5") (pintype "passive"))
    )
    (net (code "16") (name "Net-(JP19-Pad1)") (class "Default")
      (node (ref "JP19") (pin "1") (pinfunction "1_1") (pintype "passive"))
      (node (ref "JP19") (pin "2") (pinfunction "2_2") (pintype "passive"))
      (node (ref "JP19") (pin "3") (pinfunction "3_3") (pintype "passive"))
      (node (ref "JP19") (pin "4") (pinfunction "4_4") (pintype "passive"))
      (node (ref "JP19") (pin "5") (pinfunction "5_5") (pintype "passive"))
    )
    (net (code "17") (name "Net-(JP20-Pad1)") (class "Default")
      (node (ref "JP20") (pin "1") (pinfunction "1_1") (pintype "passive"))
      (node (ref "JP20") (pin "2") (pinfunction "2_2") (pintype "passive"))
      (node (ref "JP20") (pin "3") (pinfunction "3_3") (pintype "passive"))
      (node (ref "JP20") (pin "4") (pinfunction "4_4") (pintype "passive"))
      (node (ref "JP20") (pin "5") (pinfunction "5_5") (pintype "passive"))
    )
    (net (code "18") (name "Net-(JP21-Pad1)") (class "Default")
      (node (ref "JP21") (pin "1") (pinfunction "1_1") (pintype "passive"))
      (node (ref "JP21") (pin "2") (pinfunction "2_2") (pintype "passive"))
      (node (ref "JP21") (pin "3") (pinfunction "3_3") (pintype "passive"))
      (node (ref "JP21") (pin "4") (pinfunction "4_4") (pintype "passive"))
      (node (ref "JP21") (pin "5") (pinfunction "5_5") (pintype "passive"))
    )
    (net (code "19") (name "Net-(JP22-Pad1)") (class "Default")
      (node (ref "JP22") (pin "1") (pinfunction "1_1") (pintype "passive"))
      (node (ref "JP22") (pin "2") (pinfunction "2_2") (pintype "passive"))
      (node (ref "JP22") (pin "3") (pinfunction "3_3") (pintype "passive"))
      (node (ref "JP22") (pin "4") (pinfunction "4_4") (pintype "passive"))
      (node (ref "JP22") (pin "5") (pinfunction "5_5") (pintype "passive"))
    )
    (net (code "20") (name "Net-(JP23-Pad1)") (class "Default")
      (node (ref "JP23") (pin "1") (pinfunction "1_1") (pintype "passive"))
      (node (ref "JP23") (pin "2") (pinfunction "2_2") (pintype "passive"))
      (node (ref "JP23") (pin "3") (pinfunction "3_3") (pintype "passive"))
      (node (ref "JP23") (pin "4") (pinfunction "4_4") (pintype "passive"))
      (node (ref "JP23") (pin "5") (pinfunction "5_5") (pintype "passive"))
    )
    (net (code "21") (name "Net-(JP24-Pad1)") (class "Default")
      (node (ref "JP24") (pin "1") (pinfunction "1_1") (pintype "passive"))
      (node (ref "JP24") (pin "2") (pinfunction "2_2") (pintype "passive"))
      (node (ref "JP24") (pin "3") (pinfunction "3_3") (pintype "passive"))
      (node (ref "JP24") (pin "4") (pinfunction "4_4") (pintype "passive"))
      (node (ref "JP24") (pin "5") (pinfunction "5_5") (pintype "passive"))
    )
    (net (code "22") (name "Net-(JP25-Pad1)") (class "Default")
      (node (ref "JP25") (pin "1") (pinfunction "1_1") (pintype "passive"))
      (node (ref "JP25") (pin "2") (pinfunction "2_2") (pintype "passive"))
      (node (ref "JP25") (pin "3") (pinfunction "3_3") (pintype "passive"))
      (node (ref "JP25") (pin "4") (pinfunction "4_4") (pintype "passive"))
      (node (ref "JP25") (pin "5") (pinfunction "5_5") (pintype "passive"))
    )
    (net (code "23") (name "Net-(JP26-Pad1)") (class "Default")
      (node (ref "JP26") (pin "1") (pinfunction "1_1") (pintype "passive"))
      (node (ref "JP26") (pin "2") (pinfunction "2_2") (pintype "passive"))
      (node (ref "JP26") (pin "3") (pinfunction "3_3") (pintype "passive"))
      (node (ref "JP26") (pin "4") (pinfunction "4_4") (pintype "passive"))
      (node (ref "JP26") (pin "5") (pinfunction "5_5") (pintype "passive"))
    )
    (net (code "24") (name "Net-(JP27-Pad1)") (class "Default")
      (node (ref "JP27") (pin "1") (pinfunction "1_1") (pintype "passive"))
      (node (ref "JP27") (pin "2") (pinfunction "2_2") (pintype "passive"))
      (node (ref "JP27") (pin "3") (pinfunction "3_3") (pintype "passive"))
      (node (ref "JP27") (pin "4") (pinfunction "4_4") (pintype "passive"))
      (node (ref "JP27") (pin "5") (pinfunction "5_5") (pintype "passive"))
    )
    (net (code "25") (name "Net-(JP28-Pad1)") (class "Default")
      (node (ref "JP28") (pin "1") (pinfunction "1_1") (pintype "passive"))
      (node (ref "JP28") (pin "2") (pinfunction "2_2") (pintype "passive"))
      (node (ref "JP28") (pin "3") (pinfunction "3_3") (pintype "passive"))
      (node (ref "JP28") (pin "4") (pinfunction "4_4") (pintype "passive"))
      (node (ref "JP28") (pin "5") (pinfunction "5_5") (pintype "passive"))
    )
    (net (code "26") (name "Net-(JP29-Pad1)") (class "Default")
      (node (ref "JP29") (pin "1") (pinfunction "1_1") (pintype "passive"))
      (node (ref "JP29") (pin "2") (pinfunction "2_2") (pintype "passive"))
      (node (ref "JP29") (pin "3") (pinfunction "3_3") (pintype "passive"))
      (node (ref "JP29") (pin "4") (pinfunction "4_4") (pintype "passive"))
      (node (ref "JP29") (pin "5") (pinfunction "5_5") (pintype "passive"))
    )
    (net (code "27") (name "Net-(JP30-Pad1)") (class "Default")
      (node (ref "JP30") (pin "1") (pinfunction "1_1") (pintype "passive"))
      (node (ref "JP30") (pin "2") (pinfunction "2_2") (pintype "passive"))
      (node (ref "JP30") (pin "3") (pinfunction "3_3") (pintype "passive"))
      (node (ref "JP30") (pin "4") (pinfunction "4_4") (pintype "passive"))
      (node (ref "JP30") (pin "5") (pinfunction "5_5") (pintype "passive"))
    )
    (net (code "28") (name "Net-(JP31-Pad1)") (class "Default")
      (node (ref "JP31") (pin "1") (pinfunction "1_1") (pintype "passive"))
      (node (ref "JP31") (pin "2") (pinfunction "2_2") (pintype "passive"))
      (node (ref "JP31") (pin "3") (pinfunction "3_3") (pintype "passive"))
      (node (ref "JP31") (pin "4") (pinfunction "4_4") (pintype "passive"))
      (node (ref "JP31") (pin "5") (pinfunction "5_5") (pintype "passive"))
    )
    (net (code "29") (name "Net-(JP32-Pad1)") (class "Default")
      (node (ref "JP32") (pin "1") (pinfunction "1_1") (pintype "passive"))
      (node (ref "JP32") (pin "2") (pinfunction "2_2") (pintype "passive"))
      (node (ref "JP32") (pin "3") (pinfunction "3_3") (pintype "passive"))
      (node (ref "JP32") (pin "4") (pinfunction "4_4") (pintype "passive"))
      (node (ref "JP32") (pin "5") (pinfunction "5_5") (pintype "passive"))
    )
    (net (code "30") (name "Net-(JP33-Pad1)") (class "Default")
      (node (ref "JP33") (pin "1") (pinfunction "1_1") (pintype "passive"))
      (node (ref "JP33") (pin "2") (pinfunction "2_2") (pintype "passive"))
      (node (ref "JP33") (pin "3") (pinfunction "3_3") (pintype "passive"))
      (node (ref "JP33") (pin "4") (pinfunction "4_4") (pintype "passive"))
      (node (ref "JP33") (pin "5") (pinfunction "5_5") (pintype "passive"))
    )
    (net (code "31") (name "Net-(JP34-Pad1)") (class "Default")
      (node (ref "JP34") (pin "1") (pinfunction "1_1") (pintype "passive"))
      (node (ref "JP34") (pin "2") (pinfunction "2_2") (pintype "passive"))
      (node (ref "JP34") (pin "3") (pinfunction "3_3") (pintype "passive"))
      (node (ref "JP34") (pin "4") (pinfunction "4_4") (pintype "passive"))
      (node (ref "JP34") (pin "5") (pinfunction "5_5") (pintype "passive"))
    )
    (net (code "32") (name "Net-(JP35-Pad1)") (class "Default")
      (node (ref "JP35") (pin "1") (pinfunction "1_1") (pintype "passive"))
      (node (ref "JP35") (pin "2") (pinfunction "2_2") (pintype "passive"))
      (node (ref "JP35") (pin "3") (pinfunction "3_3") (pintype "passive"))
      (node (ref "JP35") (pin "4") (pinfunction "4_4") (pintype "passive"))
      (node (ref "JP35") (pin "5") (pinfunction "5_5") (pintype "passive"))
    )
    (net (code "33") (name "Net-(JP36-Pad1)") (class "Default")
      (node (ref "JP36") (pin "1") (pinfunction "1_1") (pintype "passive"))
      (node (ref "JP36") (pin "2") (pinfunction "2_2") (pintype "passive"))
      (node (ref "JP36") (pin "3") (pinfunction "3_3") (pintype "passive"))
      (node (ref "JP36") (pin "4") (pinfunction "4_4") (pintype "passive"))
      (node (ref "JP36") (pin "5") (pinfunction "5_5") (pintype "passive"))
    )
    (net (code "34") (name "Net-(JP37-Pad1)") (class "Default")
      (node (ref "JP37") (pin "1") (pinfunction "1_1") (pintype "passive"))
      (node (ref "JP37") (pin "2") (pinfunction "2_2") (pintype "passive"))
      (node (ref "JP37") (pin "3") (pinfunction "3_3") (pintype "passive"))
      (node (ref "JP37") (pin "4") (pinfunction "4_4") (pintype "passive"))
      (node (ref "JP37") (pin "5") (pinfunction "5_5") (pintype "passive"))
    )
    (net (code "35") (name "Net-(JP38-Pad1)") (class "Default")
      (node (ref "JP38") (pin "1") (pinfunction "1_1") (pintype "passive"))
      (node (ref "JP38") (pin "2") (pinfunction "2_2") (pintype "passive"))
      (node (ref "JP38") (pin "3") (pinfunction "3_3") (pintype "passive"))
      (node (ref "JP38") (pin "4") (pinfunction "4_4") (pintype "passive"))
      (node (ref "JP38") (pin "5") (pinfunction "5_5") (pintype "passive"))
    )
    (net (code "36") (name "Net-(JP39-Pad1)") (class "Default")
      (node (ref "JP39") (pin "1") (pinfunction "1_1") (pintype "passive"))
      (node (ref "JP39") (pin "2") (pinfunction "2_2") (pintype "passive"))
      (node (ref "JP39") (pin "3") (pinfunction "3_3") (pintype "passive"))
      (node (ref "JP39") (pin "4") (pinfunction "4_4") (pintype "passive"))
      (node (ref "JP39") (pin "5") (pinfunction "5_5") (pintype "passive"))
    )
    (net (code "37") (name "Net-(JP40-Pad1)") (class "Default")
      (node (ref "JP40") (pin "1") (pinfunction "1_1") (pintype "passive"))
      (node (ref "JP40") (pin "2") (pinfunction "2_2") (pintype "passive"))
      (node (ref "JP40") (pin "3") (pinfunction "3_3") (pintype "passive"))
      (node (ref "JP40") (pin "4") (pinfunction "4_4") (pintype "passive"))
      (node (ref "JP40") (pin "5") (pinfunction "5_5") (pintype "passive"))
    )
    (net (code "38") (name "Net-(JP41-Pad1)") (class "Default")
      (node (ref "JP41") (pin "1") (pinfunction "1_1") (pintype "passive"))
      (node (ref "JP41") (pin "2") (pinfunction "2_2") (pintype "passive"))
      (node (ref "JP41") (pin "3") (pinfunction "3_3") (pintype "passive"))
      (node (ref "JP41") (pin "4") (pinfunction "4_4") (pintype "passive"))
      (node (ref "JP41") (pin "5") (pinfunction "5_5") (pintype "passive"))
    )
    (net (code "39") (name "Net-(JP42-Pad1)") (class "Default")
      (node (ref "JP42") (pin "1") (pinfunction "1_1") (pintype "passive"))
      (node (ref "JP42") (pin "2") (pinfunction "2_2") (pintype "passive"))
      (node (ref "JP42") (pin "3") (pinfunction "3_3") (pintype "passive"))
      (node (ref "JP42") (pin "4") (pinfunction "4_4") (pintype "passive"))
      (node (ref "JP42") (pin "5") (pinfunction "5_5") (pintype "passive"))
    )
    (net (code "40") (name "Net-(JP43-Pad1)") (class "Default")
      (node (ref "JP43") (pin "1") (pinfunction "1_1") (pintype "passive"))
      (node (ref "JP43") (pin "2") (pinfunction "2_2") (pintype "passive"))
      (node (ref "JP43") (pin "3") (pinfunction "3_3") (pintype "passive"))
      (node (ref "JP43") (pin "4") (pinfunction "4_4") (pintype "passive"))
      (node (ref "JP43") (pin "5") (pinfunction "5_5") (pintype "passive"))
    )
    (net (code "41") (name "Net-(JP44-Pad1)") (class "Default")
      (node (ref "JP44") (pin "1") (pinfunction "1_1") (pintype "passive"))
      (node (ref "JP44") (pin "2") (pinfunction "2_2") (pintype "passive"))
      (node (ref "JP44") (pin "3") (pinfunction "3_3") (pintype "passive"))
      (node (ref "JP44") (pin "4") (pinfunction "4_4") (pintype "passive"))
      (node (ref "JP44") (pin "5") (pinfunction "5_5") (pintype "passive"))
    )
    (net (code "42") (name "Net-(JP45-Pad1)") (class "Default")
      (node (ref "JP45") (pin "1") (pinfunction "1_1") (pintype "passive"))
      (node (ref "JP45") (pin "2") (pinfunction "2_2") (pintype "passive"))
      (node (ref "JP45") (pin "3") (pinfunction "3_3") (pintype "passive"))
      (node (ref "JP45") (pin "4") (pinfunction "4_4") (pintype "passive"))
      (node (ref "JP45") (pin "5") (pinfunction "5_5") (pintype "passive"))
    )
    (net (code "43") (name "Net-(JP46-Pad1)") (class "Default")
      (node (ref "JP46") (pin "1") (pinfunction "1_1") (pintype "passive"))
      (node (ref "JP46") (pin "2") (pinfunction "2_2") (pintype "passive"))
      (node (ref "JP46") (pin "3") (pinfunction "3_3") (pintype "passive"))
      (node (ref "JP46") (pin "4") (pinfunction "4_4") (pintype "passive"))
      (node (ref "JP46") (pin "5") (pinfunction "5_5") (pintype "passive"))
    )
    (net (code "44") (name "Net-(JP47-Pad1)") (class "Default")
      (node (ref "JP47") (pin "1") (pinfunction "1_1") (pintype "passive"))
      (node (ref "JP47") (pin "2") (pinfunction "2_2") (pintype "passive"))
      (node (ref "JP47") (pin "3") (pinfunction "3_3") (pintype "passive"))
      (node (ref "JP47") (pin "4") (pinfunction "4_4") (pintype "passive"))
      (node (ref "JP47") (pin "5") (pinfunction "5_5") (pintype "passive"))
    )
    (net (code "45") (name "Net-(JP48-Pad1)") (class "Default")
      (node (ref "JP48") (pin "1") (pinfunction "1_1") (pintype "passive"))
      (node (ref "JP48") (pin "2") (pinfunction "2_2") (pintype "passive"))
      (node (ref "JP48") (pin "3") (pinfunction "3_3") (pintype "passive"))
      (node (ref "JP48") (pin "4") (pinfunction "4_4") (pintype "passive"))
      (node (ref "JP48") (pin "5") (pinfunction "5_5") (pintype "passive"))
    )
    (net (code "46") (name "Net-(JP49-Pad1)") (class "Default")
      (node (ref "JP49") (pin "1") (pinfunction "1_1") (pintype "passive"))
      (node (ref "JP49") (pin "2") (pinfunction "2_2") (pintype "passive"))
      (node (ref "JP49") (pin "3") (pinfunction "3_3") (pintype "passive"))
      (node (ref "JP49") (pin "4") (pinfunction "4_4") (pintype "passive"))
      (node (ref "JP49") (pin "5") (pinfunction "5_5") (pintype "passive"))
    )
    (net (code "47") (name "Net-(JP50-Pad1)") (class "Default")
      (node (ref "JP50") (pin "1") (pinfunction "1_1") (pintype "passive"))
      (node (ref "JP50") (pin "2") (pinfunction "2_2") (pintype "passive"))
      (node (ref "JP50") (pin "3") (pinfunction "3_3") (pintype "passive"))
      (node (ref "JP50") (pin "4") (pinfunction "4_4") (pintype "passive"))
      (node (ref "JP50") (pin "5") (pinfunction "5_5") (pintype "passive"))
    )
    (net (code "48") (name "Net-(JP51-Pad1)") (class "Default")
      (node (ref "JP51") (pin "1") (pinfunction "1_1") (pintype "passive"))
      (node (ref "JP51") (pin "2") (pinfunction "2_2") (pintype "passive"))
      (node (ref "JP51") (pin "3") (pinfunction "3_3") (pintype "passive"))
      (node (ref "JP51") (pin "4") (pinfunction "4_4") (pintype "passive"))
      (node (ref "JP51") (pin "5") (pinfunction "5_5") (pintype "passive"))
    )
    (net (code "49") (name "Net-(JP52-Pad1)") (class "Default")
      (node (ref "JP52") (pin "1") (pinfunction "1_1") (pintype "passive"))
      (node (ref "JP52") (pin "2") (pinfunction "2_2") (pintype "passive"))
      (node (ref "JP52") (pin "3") (pinfunction "3_3") (pintype "passive"))
      (node (ref "JP52") (pin "4") (pinfunction "4_4") (pintype "passive"))
      (node (ref "JP52") (pin "5") (pinfunction "5_5") (pintype "passive"))
    )
    (net (code "50") (name "Net-(JP53-Pad1)") (class "Default")
      (node (ref "JP53") (pin "1") (pinfunction "1_1") (pintype "passive"))
      (node (ref "JP53") (pin "2") (pinfunction "2_2") (pintype "passive"))
      (node (ref "JP53") (pin "3") (pinfunction "3_3") (pintype "passive"))
      (node (ref "JP53") (pin "4") (pinfunction "4_4") (pintype "passive"))
      (node (ref "JP53") (pin "5") (pinfunction "5_5") (pintype "passive"))
    )
    (net (code "51") (name "Net-(JP54-Pad1)") (class "Default")
      (node (ref "JP54") (pin "1") (pinfunction "1_1") (pintype "passive"))
      (node (ref "JP54") (pin "2") (pinfunction "2_2") (pintype "passive"))
      (node (ref "JP54") (pin "3") (pinfunction "3_3") (pintype "passive"))
      (node (ref "JP54") (pin "4") (pinfunction "4_4") (pintype "passive"))
      (node (ref "JP54") (pin "5") (pinfunction "5_5") (pintype "passive"))
    )
    (net (code "52") (name "Net-(JP55-Pad1)") (class "Default")
      (node (ref "JP55") (pin "1") (pinfunction "1_1") (pintype "passive"))
      (node (ref "JP55") (pin "2") (pinfunction "2_2") (pintype "passive"))
      (node (ref "JP55") (pin "3") (pinfunction "3_3") (pintype "passive"))
      (node (ref "JP55") (pin "4") (pinfunction "4_4") (pintype "passive"))
      (node (ref "JP55") (pin "5") (pinfunction "5_5") (pintype "passive"))
    )
    (net (code "53") (name "Net-(JP56-Pad1)") (class "Default")
      (node (ref "JP56") (pin "1") (pinfunction "1_1") (pintype "passive"))
      (node (ref "JP56") (pin "2") (pinfunction "2_2") (pintype "passive"))
      (node (ref "JP56") (pin "3") (pinfunction "3_3") (pintype "passive"))
      (node (ref "JP56") (pin "4") (pinfunction "4_4") (pintype "passive"))
      (node (ref "JP56") (pin "5") (pinfunction "5_5") (pintype "passive"))
    )
    (net (code "54") (name "Net-(JP57-Pad1)") (class "Default")
      (node (ref "JP57") (pin "1") (pinfunction "1_1") (pintype "passive"))
      (node (ref "JP57") (pin "2") (pinfunction "2_2") (pintype "passive"))
      (node (ref "JP57") (pin "3") (pinfunction "3_3") (pintype "passive"))
      (node (ref "JP57") (pin "4") (pinfunction "4_4") (pintype "passive"))
      (node (ref "JP57") (pin "5") (pinfunction "5_5") (pintype "passive"))
    )
    (net (code "55") (name "Net-(JP58-Pad1)") (class "Default")
      (node (ref "JP58") (pin "1") (pinfunction "1_1") (pintype "passive"))
      (node (ref "JP58") (pin "2") (pinfunction "2_2") (pintype "passive"))
      (node (ref "JP58") (pin "3") (pinfunction "3_3") (pintype "passive"))
      (node (ref "JP58") (pin "4") (pinfunction "4_4") (pintype "passive"))
      (node (ref "JP58") (pin "5") (pinfunction "5_5") (pintype "passive"))
    )
    (net (code "56") (name "Net-(JP59-Pad1)") (class "Default")
      (node (ref "JP59") (pin "1") (pinfunction "1_1") (pintype "passive"))
      (node (ref "JP59") (pin "2") (pinfunction "2_2") (pintype "passive"))
      (node (ref "JP59") (pin "3") (pinfunction "3_3") (pintype "passive"))
      (node (ref "JP59") (pin "4") (pinfunction "4_4") (pintype "passive"))
      (node (ref "JP59") (pin "5") (pinfunction "5_5") (pintype "passive"))
    )
    (net (code "57") (name "Net-(JP60-Pad1)") (class "Default")
      (node (ref "JP60") (pin "1") (pinfunction "1_1") (pintype "passive"))
      (node (ref "JP60") (pin "2") (pinfunction "2_2") (pintype "passive"))
      (node (ref "JP60") (pin "3") (pinfunction "3_3") (pintype "passive"))
      (node (ref "JP60") (pin "4") (pinfunction "4_4") (pintype "passive"))
      (node (ref "JP60") (pin "5") (pinfunction "5_5") (pintype "passive"))
    )
    (net (code "58") (name "Net-(JP61-Pad1)") (class "Default")
      (node (ref "JP61") (pin "1") (pinfunction "1_1") (pintype "passive"))
      (node (ref "JP61") (pin "2") (pinfunction "2_2") (pintype "passive"))
      (node (ref "JP61") (pin "3") (pinfunction "3_3") (pintype "passive"))
      (node (ref "JP61") (pin "4") (pinfunction "4_4") (pintype "passive"))
      (node (ref "JP61") (pin "5") (pinfunction "5_5") (pintype "passive"))
    )
    (net (code "59") (name "Net-(JP62-Pad1)") (class "Default")
      (node (ref "JP62") (pin "1") (pinfunction "1_1") (pintype "passive"))
      (node (ref "JP62") (pin "2") (pinfunction "2_2") (pintype "passive"))
      (node (ref "JP62") (pin "3") (pinfunction "3_3") (pintype "passive"))
      (node (ref "JP62") (pin "4") (pinfunction "4_4") (pintype "passive"))
      (node (ref "JP62") (pin "5") (pinfunction "5_5") (pintype "passive"))
    )
    (net (code "60") (name "Net-(JP63-Pad1)") (class "Default")
      (node (ref "JP63") (pin "1") (pinfunction "1_1") (pintype "passive"))
      (node (ref "JP63") (pin "2") (pinfunction "2_2") (pintype "passive"))
      (node (ref "JP63") (pin "3") (pinfunction "3_3") (pintype "passive"))
      (node (ref "JP63") (pin "4") (pinfunction "4_4") (pintype "passive"))
      (node (ref "JP63") (pin "5") (pinfunction "5_5") (pintype "passive"))
    )
    (net (code "61") (name "Net-(JP64-Pad1)") (class "Default")
      (node (ref "JP64") (pin "1") (pinfunction "1_1") (pintype "passive"))
      (node (ref "JP64") (pin "2") (pinfunction "2_2") (pintype "passive"))
      (node (ref "JP64") (pin "3") (pinfunction "3_3") (pintype "passive"))
      (node (ref "JP64") (pin "4") (pinfunction "4_4") (pintype "passive"))
      (node (ref "JP64") (pin "5") (pinfunction "5_5") (pintype "passive"))
    )
    (net (code "62") (name "Net-(JP69-Pad1)") (class "Default")
      (node (ref "JP69") (pin "1") (pinfunction "1_1") (pintype "passive"))
      (node (ref "JP69") (pin "2") (pinfunction "2_2") (pintype "passive"))
      (node (ref "JP69") (pin "3") (pinfunction "3_3") (pintype "passive"))
      (node (ref "JP69") (pin "4") (pinfunction "4_4") (pintype "passive"))
      (node (ref "JP69") (pin "5") (pinfunction "5_5") (pintype "passive"))
    )
    (net (code "63") (name "Net-(JP70-Pad1)") (class "Default")
      (node (ref "JP70") (pin "1") (pinfunction "1_1") (pintype "passive"))
      (node (ref "JP70") (pin "2") (pinfunction "2_2") (pintype "passive"))
      (node (ref "JP70") (pin "3") (pinfunction "3_3") (pintype "passive"))
      (node (ref "JP70") (pin "4") (pinfunction "4_4") (pintype "passive"))
      (node (ref "JP70") (pin "5") (pinfunction "5_5") (pintype "passive"))
    )
    (net (code "64") (name "Net-(JP71-Pad1)") (class "Default")
      (node (ref "JP71") (pin "1") (pinfunction "1_1") (pintype "passive"))
      (node (ref "JP71") (pin "2") (pinfunction "2_2") (pintype "passive"))
      (node (ref "JP71") (pin "3") (pinfunction "3_3") (pintype "passive"))
      (node (ref "JP71") (pin "4") (pinfunction "4_4") (pintype "passive"))
      (node (ref "JP71") (pin "5") (pinfunction "5_5") (pintype "passive"))
    )
    (net (code "65") (name "Net-(JP72-Pad1)") (class "Default")
      (node (ref "JP72") (pin "1") (pinfunction "1_1") (pintype "passive"))
      (node (ref "JP72") (pin "2") (pinfunction "2_2") (pintype "passive"))
      (node (ref "JP72") (pin "3") (pinfunction "3_3") (pintype "passive"))
      (node (ref "JP72") (pin "4") (pinfunction "4_4") (pintype "passive"))
      (node (ref "JP72") (pin "5") (pinfunction "5_5") (pintype "passive"))
    )
    (net (code "66") (name "Net-(JP73-Pad1)") (class "Default")
      (node (ref "JP73") (pin "1") (pinfunction "1_1") (pintype "passive"))
      (node (ref "JP73") (pin "2") (pinfunction "2_2") (pintype "passive"))
      (node (ref "JP73") (pin "3") (pinfunction "3_3") (pintype "passive"))
      (node (ref "JP73") (pin "4") (pinfunction "4_4") (pintype "passive"))
      (node (ref "JP73") (pin "5") (pinfunction "5_5") (pintype "passive"))
    )
    (net (code "67") (name "Net-(JP74-Pad1)") (class "Default")
      (node (ref "JP74") (pin "1") (pinfunction "1_1") (pintype "passive"))
      (node (ref "JP74") (pin "2") (pinfunction "2_2") (pintype "passive"))
      (node (ref "JP74") (pin "3") (pinfunction "3_3") (pintype "passive"))
      (node (ref "JP74") (pin "4") (pinfunction "4_4") (pintype "passive"))
      (node (ref "JP74") (pin "5") (pinfunction "5_5") (pintype "passive"))
    )
    (net (code "68") (name "Net-(JP75-Pad1)") (class "Default")
      (node (ref "JP75") (pin "1") (pinfunction "1_1") (pintype "passive"))
      (node (ref "JP75") (pin "2") (pinfunction "2_2") (pintype "passive"))
      (node (ref "JP75") (pin "3") (pinfunction "3_3") (pintype "passive"))
      (node (ref "JP75") (pin "4") (pinfunction "4_4") (pintype "passive"))
      (node (ref "JP75") (pin "5") (pinfunction "5_5") (pintype "passive"))
    )
    (net (code "69") (name "Net-(JP76-Pad1)") (class "Default")
      (node (ref "JP76") (pin "1") (pinfunction "1_1") (pintype "passive"))
      (node (ref "JP76") (pin "2") (pinfunction "2_2") (pintype "passive"))
      (node (ref "JP76") (pin "3") (pinfunction "3_3") (pintype "passive"))
      (node (ref "JP76") (pin "4") (pinfunction "4_4") (pintype "passive"))
      (node (ref "JP76") (pin "5") (pinfunction "5_5") (pintype "passive"))
    )
    (net (code "70") (name "Net-(JP77-Pad1)") (class "Default")
      (node (ref "JP77") (pin "1") (pinfunction "1_1") (pintype "passive"))
      (node (ref "JP77") (pin "2") (pinfunction "2_2") (pintype "passive"))
      (node (ref "JP77") (pin "3") (pinfunction "3_3") (pintype "passive"))
      (node (ref "JP77") (pin "4") (pinfunction "4_4") (pintype "passive"))
      (node (ref "JP77") (pin "5") (pinfunction "5_5") (pintype "passive"))
    )
    (net (code "71") (name "Net-(JP78-Pad1)") (class "Default")
      (node (ref "JP78") (pin "1") (pinfunction "1_1") (pintype "passive"))
      (node (ref "JP78") (pin "2") (pinfunction "2_2") (pintype "passive"))
      (node (ref "JP78") (pin "3") (pinfunction "3_3") (pintype "passive"))
      (node (ref "JP78") (pin "4") (pinfunction "4_4") (pintype "passive"))
      (node (ref "JP78") (pin "5") (pinfunction "5_5") (pintype "passive"))
    )
    (net (code "72") (name "Net-(JP79-Pad1)") (class "Default")
      (node (ref "JP79") (pin "1") (pinfunction "1_1") (pintype "passive"))
      (node (ref "JP79") (pin "2") (pinfunction "2_2") (pintype "passive"))
      (node (ref "JP79") (pin "3") (pinfunction "3_3") (pintype "passive"))
      (node (ref "JP79") (pin "4") (pinfunction "4_4") (pintype "passive"))
      (node (ref "JP79") (pin "5") (pinfunction "5_5") (pintype "passive"))
    )
    (net (code "73") (name "Net-(JP80-Pad1)") (class "Default")
      (node (ref "JP80") (pin "1") (pinfunction "1_1") (pintype "passive"))
      (node (ref "JP80") (pin "2") (pinfunction "2_2") (pintype "passive"))
      (node (ref "JP80") (pin "3") (pinfunction "3_3") (pintype "passive"))
      (node (ref "JP80") (pin "4") (pinfunction "4_4") (pintype "passive"))
      (node (ref "JP80") (pin "5") (pinfunction "5_5") (pintype "passive"))
    )
    (net (code "74") (name "Net-(JP81-Pad1)") (class "Default")
      (node (ref "JP81") (pin "1") (pinfunction "1_1") (pintype "passive"))
      (node (ref "JP81") (pin "2") (pinfunction "2_2") (pintype "passive"))
      (node (ref "JP81") (pin "3") (pinfunction "3_3") (pintype "passive"))
      (node (ref "JP81") (pin "4") (pinfunction "4_4") (pintype "passive"))
      (node (ref "JP81") (pin "5") (pinfunction "5_5") (pintype "passive"))
    )
    (net (code "75") (name "Net-(JP82-Pad1)") (class "Default")
      (node (ref "JP82") (pin "1") (pinfunction "1_1") (pintype "passive"))
      (node (ref "JP82") (pin "2") (pinfunction "2_2") (pintype "passive"))
      (node (ref "JP82") (pin "3") (pinfunction "3_3") (pintype "passive"))
      (node (ref "JP82") (pin "4") (pinfunction "4_4") (pintype "passive"))
      (node (ref "JP82") (pin "5") (pinfunction "5_5") (pintype "passive"))
    )
    (net (code "76") (name "Net-(JP83-Pad1)") (class "Default")
      (node (ref "JP83") (pin "1") (pinfunction "1_1") (pintype "passive"))
      (node (ref "JP83") (pin "2") (pinfunction "2_2") (pintype "passive"))
      (node (ref "JP83") (pin "3") (pinfunction "3_3") (pintype "passive"))
      (node (ref "JP83") (pin "4") (pinfunction "4_4") (pintype "passive"))
      (node (ref "JP83") (pin "5") (pinfunction "5_5") (pintype "passive"))
    )
    (net (code "77") (name "Net-(JP84-Pad1)") (class "Default")
      (node (ref "JP84") (pin "1") (pinfunction "1_1") (pintype "passive"))
      (node (ref "JP84") (pin "2") (pinfunction "2_2") (pintype "passive"))
      (node (ref "JP84") (pin "3") (pinfunction "3_3") (pintype "passive"))
      (node (ref "JP84") (pin "4") (pinfunction "4_4") (pintype "passive"))
      (node (ref "JP84") (pin "5") (pinfunction "5_5") (pintype "passive"))
    )
    (net (code "78") (name "Net-(JP85-Pad1)") (class "Default")
      (node (ref "JP85") (pin "1") (pinfunction "1_1") (pintype "passive"))
      (node (ref "JP85") (pin "2") (pinfunction "2_2") (pintype "passive"))
      (node (ref "JP85") (pin "3") (pinfunction "3_3") (pintype "passive"))
      (node (ref "JP85") (pin "4") (pinfunction "4_4") (pintype "passive"))
      (node (ref "JP85") (pin "5") (pinfunction "5_5") (pintype "passive"))
    )
    (net (code "79") (name "Net-(JP86-Pad1)") (class "Default")
      (node (ref "JP86") (pin "1") (pinfunction "1_1") (pintype "passive"))
      (node (ref "JP86") (pin "2") (pinfunction "2_2") (pintype "passive"))
      (node (ref "JP86") (pin "3") (pinfunction "3_3") (pintype "passive"))
      (node (ref "JP86") (pin "4") (pinfunction "4_4") (pintype "passive"))
      (node (ref "JP86") (pin "5") (pinfunction "5_5") (pintype "passive"))
    )
    (net (code "80") (name "Net-(JP87-Pad1)") (class "Default")
      (node (ref "JP87") (pin "1") (pinfunction "1_1") (pintype "passive"))
      (node (ref "JP87") (pin "2") (pinfunction "2_2") (pintype "passive"))
      (node (ref "JP87") (pin "3") (pinfunction "3_3") (pintype "passive"))
      (node (ref "JP87") (pin "4") (pinfunction "4_4") (pintype "passive"))
      (node (ref "JP87") (pin "5") (pinfunction "5_5") (pintype "passive"))
    )
    (net (code "81") (name "Net-(JP88-Pad1)") (class "Default")
      (node (ref "JP88") (pin "1") (pinfunction "1_1") (pintype "passive"))
      (node (ref "JP88") (pin "2") (pinfunction "2_2") (pintype "passive"))
      (node (ref "JP88") (pin "3") (pinfunction "3_3") (pintype "passive"))
      (node (ref "JP88") (pin "4") (pinfunction "4_4") (pintype "passive"))
      (node (ref "JP88") (pin "5") (pinfunction "5_5") (pintype "passive"))
    )
    (net (code "82") (name "Net-(JP89-Pad1)") (class "Default")
      (node (ref "JP89") (pin "1") (pinfunction "1_1") (pintype "passive"))
      (node (ref "JP89") (pin "2") (pinfunction "2_2") (pintype "passive"))
      (node (ref "JP89") (pin "3") (pinfunction "3_3") (pintype "passive"))
      (node (ref "JP89") (pin "4") (pinfunction "4_4") (pintype "passive"))
      (node (ref "JP89") (pin "5") (pinfunction "5_5") (pintype "passive"))
    )
    (net (code "83") (name "Net-(JP90-Pad1)") (class "Default")
      (node (ref "JP90") (pin "1") (pinfunction "1_1") (pintype "passive"))
      (node (ref "JP90") (pin "2") (pinfunction "2_2") (pintype "passive"))
      (node (ref "JP90") (pin "3") (pinfunction "3_3") (pintype "passive"))
      (node (ref "JP90") (pin "4") (pinfunction "4_4") (pintype "passive"))
      (node (ref "JP90") (pin "5") (pinfunction "5_5") (pintype "passive"))
    )
    (net (code "84") (name "Net-(JP91-Pad1)") (class "Default")
      (node (ref "JP91") (pin "1") (pinfunction "1_1") (pintype "passive"))
      (node (ref "JP91") (pin "2") (pinfunction "2_2") (pintype "passive"))
      (node (ref "JP91") (pin "3") (pinfunction "3_3") (pintype "passive"))
      (node (ref "JP91") (pin "4") (pinfunction "4_4") (pintype "passive"))
      (node (ref "JP91") (pin "5") (pinfunction "5_5") (pintype "passive"))
    )
    (net (code "85") (name "Net-(JP92-Pad1)") (class "Default")
      (node (ref "JP92") (pin "1") (pinfunction "1_1") (pintype "passive"))
      (node (ref "JP92") (pin "2") (pinfunction "2_2") (pintype "passive"))
      (node (ref "JP92") (pin "3") (pinfunction "3_3") (pintype "passive"))
      (node (ref "JP92") (pin "4") (pinfunction "4_4") (pintype "passive"))
      (node (ref "JP92") (pin "5") (pinfunction "5_5") (pintype "passive"))
    )
    (net (code "86") (name "Net-(JP93-Pad1)") (class "Default")
      (node (ref "JP93") (pin "1") (pinfunction "1_1") (pintype "passive"))
      (node (ref "JP93") (pin "2") (pinfunction "2_2") (pintype "passive"))
      (node (ref "JP93") (pin "3") (pinfunction "3_3") (pintype "passive"))
      (node (ref "JP93") (pin "4") (pinfunction "4_4") (pintype "passive"))
      (node (ref "JP93") (pin "5") (pinfunction "5_5") (pintype "passive"))
    )
    (net (code "87") (name "Net-(JP94-Pad1)") (class "Default")
      (node (ref "JP94") (pin "1") (pinfunction "1_1") (pintype "passive"))
      (node (ref "JP94") (pin "2") (pinfunction "2_2") (pintype "passive"))
      (node (ref "JP94") (pin "3") (pinfunction "3_3") (pintype "passive"))
      (node (ref "JP94") (pin "4") (pinfunction "4_4") (pintype "passive"))
      (node (ref "JP94") (pin "5") (pinfunction "5_5") (pintype "passive"))
    )
    (net (code "88") (name "Net-(JP95-Pad1)") (class "Default")
      (node (ref "JP95") (pin "1") (pinfunction "1_1") (pintype "passive"))
      (node (ref "JP95") (pin "2") (pinfunction "2_2") (pintype "passive"))
      (node (ref "JP95") (pin "3") (pinfunction "3_3") (pintype "passive"))
      (node (ref "JP95") (pin "4") (pinfunction "4_4") (pintype "passive"))
      (node (ref "JP95") (pin "5") (pinfunction "5_5") (pintype "passive"))
    )
    (net (code "89") (name "Net-(JP96-Pad1)") (class "Default")
      (node (ref "JP96") (pin "1") (pinfunction "1_1") (pintype "passive"))
      (node (ref "JP96") (pin "2") (pinfunction "2_2") (pintype "passive"))
      (node (ref "JP96") (pin "3") (pinfunction "3_3") (pintype "passive"))
      (node (ref "JP96") (pin "4") (pinfunction "4_4") (pintype "passive"))
      (node (ref "JP96") (pin "5") (pinfunction "5_5") (pintype "passive"))
    )
    (net (code "90") (name "Net-(JP97-Pad1)") (class "Default")
      (node (ref "JP97") (pin "1") (pinfunction "1_1") (pintype "passive"))
      (node (ref "JP97") (pin "2") (pinfunction "2_2") (pintype "passive"))
      (node (ref "JP97") (pin "3") (pinfunction "3_3") (pintype "passive"))
      (node (ref "JP97") (pin "4") (pinfunction "4_4") (pintype "passive"))
      (node (ref "JP97") (pin "5") (pinfunction "5_5") (pintype "passive"))
    )
    (net (code "91") (name "Net-(JP98-Pad1)") (class "Default")
      (node (ref "JP98") (pin "1") (pinfunction "1_1") (pintype "passive"))
      (node (ref "JP98") (pin "2") (pinfunction "2_2") (pintype "passive"))
      (node (ref "JP98") (pin "3") (pinfunction "3_3") (pintype "passive"))
      (node (ref "JP98") (pin "4") (pinfunction "4_4") (pintype "passive"))
      (node (ref "JP98") (pin "5") (pinfunction "5_5") (pintype "passive"))
    )
    (net (code "92") (name "Net-(JP99-Pad1)") (class "Default")
      (node (ref "JP99") (pin "1") (pinfunction "1_1") (pintype "passive"))
      (node (ref "JP99") (pin "2") (pinfunction "2_2") (pintype "passive"))
      (node (ref "JP99") (pin "3") (pinfunction "3_3") (pintype "passive"))
      (node (ref "JP99") (pin "4") (pinfunction "4_4") (pintype "passive"))
      (node (ref "JP99") (pin "5") (pinfunction "5_5") (pintype "passive"))
    )
    (net (code "93") (name "Net-(JP100-Pad1)") (class "Default")
      (node (ref "JP100") (pin "1") (pinfunction "1_1") (pintype "passive"))
      (node (ref "JP100") (pin "2") (pinfunction "2_2") (pintype "passive"))
      (node (ref "JP100") (pin "3") (pinfunction "3_3") (pintype "passive"))
      (node (ref "JP100") (pin "4") (pinfunction "4_4") (pintype "passive"))
      (node (ref "JP100") (pin "5") (pinfunction "5_5") (pintype "passive"))
    )
    (net (code "94") (name "Net-(JP101-Pad1)") (class "Default")
      (node (ref "JP101") (pin "1") (pinfunction "1_1") (pintype "passive"))
      (node (ref "JP101") (pin "2") (pinfunction "2_2") (pintype "passive"))
      (node (ref "JP101") (pin "3") (pinfunction "3_3") (pintype "passive"))
      (node (ref "JP101") (pin "4") (pinfunction "4_4") (pintype "passive"))
      (node (ref "JP101") (pin "5") (pinfunction "5_5") (pintype "passive"))
    )
    (net (code "95") (name "Net-(JP102-Pad1)") (class "Default")
      (node (ref "JP102") (pin "1") (pinfunction "1_1") (pintype "passive"))
      (node (ref "JP102") (pin "2") (pinfunction "2_2") (pintype "passive"))
      (node (ref "JP102") (pin "3") (pinfunction "3_3") (pintype "passive"))
      (node (ref "JP102") (pin "4") (pinfunction "4_4") (pintype "passive"))
      (node (ref "JP102") (pin "5") (pinfunction "5_5") (pintype "passive"))
    )
    (net (code "96") (name "Net-(JP103-Pad1)") (class "Default")
      (node (ref "JP103") (pin "1") (pinfunction "1_1") (pintype "passive"))
      (node (ref "JP103") (pin "2") (pinfunction "2_2") (pintype "passive"))
      (node (ref "JP103") (pin "3") (pinfunction "3_3") (pintype "passive"))
      (node (ref "JP103") (pin "4") (pinfunction "4_4") (pintype "passive"))
      (node (ref "JP103") (pin "5") (pinfunction "5_5") (pintype "passive"))
    )
    (net (code "97") (name "Net-(JP104-Pad1)") (class "Default")
      (node (ref "JP104") (pin "1") (pinfunction "1_1") (pintype "passive"))
      (node (ref "JP104") (pin "2") (pinfunction "2_2") (pintype "passive"))
      (node (ref "JP104") (pin "3") (pinfunction "3_3") (pintype "passive"))
      (node (ref "JP104") (pin "4") (pinfunction "4_4") (pintype "passive"))
      (node (ref "JP104") (pin "5") (pinfunction "5_5") (pintype "passive"))
    )
    (net (code "98") (name "Net-(JP105-Pad1)") (class "Default")
      (node (ref "JP105") (pin "1") (pinfunction "1_1") (pintype "passive"))
      (node (ref "JP105") (pin "2") (pinfunction "2_2") (pintype "passive"))
      (node (ref "JP105") (pin "3") (pinfunction "3_3") (pintype "passive"))
      (node (ref "JP105") (pin "4") (pinfunction "4_4") (pintype "passive"))
      (node (ref "JP105") (pin "5") (pinfunction "5_5") (pintype "passive"))
    )
    (net (code "99") (name "Net-(JP106-Pad1)") (class "Default")
      (node (ref "JP106") (pin "1") (pinfunction "1_1") (pintype "passive"))
      (node (ref "JP106") (pin "2") (pinfunction "2_2") (pintype "passive"))
      (node (ref "JP106") (pin "3") (pinfunction "3_3") (pintype "passive"))
      (node (ref "JP106") (pin "4") (pinfunction "4_4") (pintype "passive"))
      (node (ref "JP106") (pin "5") (pinfunction "5_5") (pintype "passive"))
    )
    (net (code "100") (name "Net-(JP107-Pad1)") (class "Default")
      (node (ref "JP107") (pin "1") (pinfunction "1_1") (pintype "passive"))
      (node (ref "JP107") (pin "2") (pinfunction "2_2") (pintype "passive"))
      (node (ref "JP107") (pin "3") (pinfunction "3_3") (pintype "passive"))
      (node (ref "JP107") (pin "4") (pinfunction "4_4") (pintype "passive"))
      (node (ref "JP107") (pin "5") (pinfunction "5_5") (pintype "passive"))
    )
    (net (code "101") (name "Net-(JP108-Pad1)") (class "Default")
      (node (ref "JP108") (pin "1") (pinfunction "1_1") (pintype "passive"))
      (node (ref "JP108") (pin "2") (pinfunction "2_2") (pintype "passive"))
      (node (ref "JP108") (pin "3") (pinfunction "3_3") (pintype "passive"))
      (node (ref "JP108") (pin "4") (pinfunction "4_4") (pintype "passive"))
      (node (ref "JP108") (pin "5") (pinfunction "5_5") (pintype "passive"))
    )
    (net (code "102") (name "Net-(JP109-Pad1)") (class "Default")
      (node (ref "JP109") (pin "1") (pinfunction "1_1") (pintype "passive"))
      (node (ref "JP109") (pin "2") (pinfunction "2_2") (pintype "passive"))
      (node (ref "JP109") (pin "3") (pinfunction "3_3") (pintype "passive"))
      (node (ref "JP109") (pin "4") (pinfunction "4_4") (pintype "passive"))
      (node (ref "JP109") (pin "5") (pinfunction "5_5") (pintype "passive"))
    )
    (net (code "103") (name "Net-(JP110-Pad1)") (class "Default")
      (node (ref "JP110") (pin "1") (pinfunction "1_1") (pintype "passive"))
      (node (ref "JP110") (pin "2") (pinfunction "2_2") (pintype "passive"))
      (node (ref "JP110") (pin "3") (pinfunction "3_3") (pintype "passive"))
      (node (ref "JP110") (pin "4") (pinfunction "4_4") (pintype "passive"))
      (node (ref "JP110") (pin "5") (pinfunction "5_5") (pintype "passive"))
    )
    (net (code "104") (name "Net-(JP111-Pad1)") (class "Default")
      (node (ref "JP111") (pin "1") (pinfunction "1_1") (pintype "passive"))
      (node (ref "JP111") (pin "2") (pinfunction "2_2") (pintype "passive"))
      (node (ref "JP111") (pin "3") (pinfunction "3_3") (pintype "passive"))
      (node (ref "JP111") (pin "4") (pinfunction "4_4") (pintype "passive"))
      (node (ref "JP111") (pin "5") (pinfunction "5_5") (pintype "passive"))
    )
    (net (code "105") (name "Net-(JP112-Pad1)") (class "Default")
      (node (ref "JP112") (pin "1") (pinfunction "1_1") (pintype "passive"))
      (node (ref "JP112") (pin "2") (pinfunction "2_2") (pintype "passive"))
      (node (ref "JP112") (pin "3") (pinfunction "3_3") (pintype "passive"))
      (node (ref "JP112") (pin "4") (pinfunction "4_4") (pintype "passive"))
      (node (ref "JP112") (pin "5") (pinfunction "5_5") (pintype "passive"))
    )
    (net (code "106") (name "Net-(JP113-Pad1)") (class "Default")
      (node (ref "JP113") (pin "1") (pinfunction "1_1") (pintype "passive"))
      (node (ref "JP113") (pin "2") (pinfunction "2_2") (pintype "passive"))
      (node (ref "JP113") (pin "3") (pinfunction "3_3") (pintype "passive"))
      (node (ref "JP113") (pin "4") (pinfunction "4_4") (pintype "passive"))
      (node (ref "JP113") (pin "5") (pinfunction "5_5") (pintype "passive"))
    )
    (net (code "107") (name "Net-(JP114-Pad1)") (class "Default")
      (node (ref "JP114") (pin "1") (pinfunction "1_1") (pintype "passive"))
      (node (ref "JP114") (pin "2") (pinfunction "2_2") (pintype "passive"))
      (node (ref "JP114") (pin "3") (pinfunction "3_3") (pintype "passive"))
      (node (ref "JP114") (pin "4") (pinfunction "4_4") (pintype "passive"))
      (node (ref "JP114") (pin "5") (pinfunction "5_5") (pintype "passive"))
    )
    (net (code "108") (name "Net-(JP115-Pad1)") (class "Default")
      (node (ref "JP115") (pin "1") (pinfunction "1_1") (pintype "passive"))
      (node (ref "JP115") (pin "2") (pinfunction "2_2") (pintype "passive"))
      (node (ref "JP115") (pin "3") (pinfunction "3_3") (pintype "passive"))
      (node (ref "JP115") (pin "4") (pinfunction "4_4") (pintype "passive"))
      (node (ref "JP115") (pin "5") (pinfunction "5_5") (pintype "passive"))
    )
    (net (code "109") (name "Net-(JP116-Pad1)") (class "Default")
      (node (ref "JP116") (pin "1") (pinfunction "1_1") (pintype "passive"))
      (node (ref "JP116") (pin "2") (pinfunction "2_2") (pintype "passive"))
      (node (ref "JP116") (pin "3") (pinfunction "3_3") (pintype "passive"))
      (node (ref "JP116") (pin "4") (pinfunction "4_4") (pintype "passive"))
      (node (ref "JP116") (pin "5") (pinfunction "5_5") (pintype "passive"))
    )
    (net (code "110") (name "Net-(JP117-Pad1)") (class "Default")
      (node (ref "JP117") (pin "1") (pinfunction "1_1") (pintype "passive"))
      (node (ref "JP117") (pin "2") (pinfunction "2_2") (pintype "passive"))
      (node (ref "JP117") (pin "3") (pinfunction "3_3") (pintype "passive"))
      (node (ref "JP117") (pin "4") (pinfunction "4_4") (pintype "passive"))
      (node (ref "JP117") (pin "5") (pinfunction "5_5") (pintype "passive"))
    )
    (net (code "111") (name "Net-(JP118-Pad1)") (class "Default")
      (node (ref "JP118") (pin "1") (pinfunction "1_1") (pintype "passive"))
      (node (ref "JP118") (pin "2") (pinfunction "2_2") (pintype "passive"))
      (node (ref "JP118") (pin "3") (pinfunction "3_3") (pintype "passive"))
      (node (ref "JP118") (pin "4") (pinfunction "4_4") (pintype "passive"))
      (node (ref "JP118") (pin "5") (pinfunction "5_5") (pintype "passive"))
    )
    (net (code "112") (name "Net-(JP119-Pad1)") (class "Default")
      (node (ref "JP119") (pin "1") (pinfunction "1_1") (pintype "passive"))
      (node (ref "JP119") (pin "2") (pinfunction "2_2") (pintype "passive"))
      (node (ref "JP119") (pin "3") (pinfunction "3_3") (pintype "passive"))
      (node (ref "JP119") (pin "4") (pinfunction "4_4") (pintype "passive"))
      (node (ref "JP119") (pin "5") (pinfunction "5_5") (pintype "passive"))
    )
    (net (code "113") (name "Net-(JP120-Pad1)") (class "Default")
      (node (ref "JP120") (pin "1") (pinfunction "1_1") (pintype "passive"))
      (node (ref "JP120") (pin "2") (pinfunction "2_2") (pintype "passive"))
      (node (ref "JP120") (pin "3") (pinfunction "3_3") (pintype "passive"))
      (node (ref "JP120") (pin "4") (pinfunction "4_4") (pintype "passive"))
      (node (ref "JP120") (pin "5") (pinfunction "5_5") (pintype "passive"))
    )
    (net (code "114") (name "Net-(JP121-Pad1)") (class "Default")
      (node (ref "JP121") (pin "1") (pinfunction "1_1") (pintype "passive"))
      (node (ref "JP121") (pin "2") (pinfunction "2_2") (pintype "passive"))
      (node (ref "JP121") (pin "3") (pinfunction "3_3") (pintype "passive"))
      (node (ref "JP121") (pin "4") (pinfunction "4_4") (pintype "passive"))
      (node (ref "JP121") (pin "5") (pinfunction "5_5") (pintype "passive"))
    )
    (net (code "115") (name "Net-(JP122-Pad1)") (class "Default")
      (node (ref "JP122") (pin "1") (pinfunction "1_1") (pintype "passive"))
      (node (ref "JP122") (pin "2") (pinfunction "2_2") (pintype "passive"))
      (node (ref "JP122") (pin "3") (pinfunction "3_3") (pintype "passive"))
      (node (ref "JP122") (pin "4") (pinfunction "4_4") (pintype "passive"))
      (node (ref "JP122") (pin "5") (pinfunction "5_5") (pintype "passive"))
    )
    (net (code "116") (name "Net-(JP123-Pad1)") (class "Default")
      (node (ref "JP123") (pin "1") (pinfunction "1_1") (pintype "passive"))
      (node (ref "JP123") (pin "2") (pinfunction "2_2") (pintype "passive"))
      (node (ref "JP123") (pin "3") (pinfunction "3_3") (pintype "passive"))
      (node (ref "JP123") (pin "4") (pinfunction "4_4") (pintype "passive"))
      (node (ref "JP123") (pin "5") (pinfunction "5_5") (pintype "passive"))
    )
    (net (code "117") (name "Net-(JP124-Pad1)") (class "Default")
      (node (ref "JP124") (pin "1") (pinfunction "1_1") (pintype "passive"))
      (node (ref "JP124") (pin "2") (pinfunction "2_2") (pintype "passive"))
      (node (ref "JP124") (pin "3") (pinfunction "3_3") (pintype "passive"))
      (node (ref "JP124") (pin "4") (pinfunction "4_4") (pintype "passive"))
      (node (ref "JP124") (pin "5") (pinfunction "5_5") (pintype "passive"))
    )
    (net (code "118") (name "Net-(JP125-Pad1)") (class "Default")
      (node (ref "JP125") (pin "1") (pinfunction "1_1") (pintype "passive"))
      (node (ref "JP125") (pin "2") (pinfunction "2_2") (pintype "passive"))
      (node (ref "JP125") (pin "3") (pinfunction "3_3") (pintype "passive"))
      (node (ref "JP125") (pin "4") (pinfunction "4_4") (pintype "passive"))
      (node (ref "JP125") (pin "5") (pinfunction "5_5") (pintype "passive"))
    )
    (net (code "119") (name "Net-(JP126-Pad1)") (class "Default")
      (node (ref "JP126") (pin "1") (pinfunction "1_1") (pintype "passive"))
      (node (ref "JP126") (pin "2") (pinfunction "2_2") (pintype "passive"))
      (node (ref "JP126") (pin "3") (pinfunction "3_3") (pintype "passive"))
      (node (ref "JP126") (pin "4") (pinfunction "4_4") (pintype "passive"))
      (node (ref "JP126") (pin "5") (pinfunction "5_5") (pintype "passive"))
    )
    (net (code "120") (name "Net-(JP127-Pad1)") (class "Default")
      (node (ref "JP127") (pin "1") (pinfunction "1_1") (pintype "passive"))
      (node (ref "JP127") (pin "2") (pinfunction "2_2") (pintype "passive"))
      (node (ref "JP127") (pin "3") (pinfunction "3_3") (pintype "passive"))
      (node (ref "JP127") (pin "4") (pinfunction "4_4") (pintype "passive"))
      (node (ref "JP127") (pin "5") (pinfunction "5_5") (pintype "passive"))
    )
    (net (code "121") (name "Net-(JP128-Pad1)") (class "Default")
      (node (ref "JP128") (pin "1") (pinfunction "1_1") (pintype "passive"))
      (node (ref "JP128") (pin "2") (pinfunction "2_2") (pintype "passive"))
      (node (ref "JP128") (pin "3") (pinfunction "3_3") (pintype "passive"))
      (node (ref "JP128") (pin "4") (pinfunction "4_4") (pintype "passive"))
      (node (ref "JP128") (pin "5") (pinfunction "5_5") (pintype "passive"))
    )
    (net (code "122") (name "Net-(JP130-Pad1)") (class "Default")
      (node (ref "JP130") (pin "1") (pinfunction "1_1") (pintype "passive"))
      (node (ref "JP130") (pin "10") (pinfunction "10_10") (pintype "passive"))
      (node (ref "JP130") (pin "11") (pinfunction "11_11") (pintype "passive"))
      (node (ref "JP130") (pin "12") (pinfunction "12_12") (pintype "passive"))
      (node (ref "JP130") (pin "13") (pinfunction "13_13") (pintype "passive"))
      (node (ref "JP130") (pin "14") (pinfunction "14_14") (pintype "passive"))
      (node (ref "JP130") (pin "15") (pinfunction "15_15") (pintype "passive"))
      (node (ref "JP130") (pin "16") (pinfunction "16_16") (pintype "passive"))
      (node (ref "JP130") (pin "17") (pinfunction "17_17") (pintype "passive"))
      (node (ref "JP130") (pin "18") (pinfunction "18_18") (pintype "passive"))
      (node (ref "JP130") (pin "19") (pinfunction "19_19") (pintype "passive"))
      (node (ref "JP130") (pin "2") (pinfunction "2_2") (pintype "passive"))
      (node (ref "JP130") (pin "20") (pinfunction "20_20") (pintype "passive"))
      (node (ref "JP130") (pin "21") (pinfunction "21_21") (pintype "passive"))
      (node (ref "JP130") (pin "22") (pinfunction "22_22") (pintype "passive"))
      (node (ref "JP130") (pin "23") (pinfunction "23_23") (pintype "passive"))
      (node (ref "JP130") (pin "24") (pinfunction "24_24") (pintype "passive"))
      (node (ref "JP130") (pin "25") (pinfunction "25_25") (pintype "passive"))
      (node (ref "JP130") (pin "26") (pinfunction "26_26") (pintype "passive"))
      (node (ref "JP130") (pin "27") (pinfunction "27_27") (pintype "passive"))
      (node (ref "JP130") (pin "28") (pinfunction "28_28") (pintype "passive"))
      (node (ref "JP130") (pin "29") (pinfunction "29_29") (pintype "passive"))
      (node (ref "JP130") (pin "3") (pinfunction "3_3") (pintype "passive"))
      (node (ref "JP130") (pin "4") (pinfunction "4_4") (pintype "passive"))
      (node (ref "JP130") (pin "5") (pinfunction "5_5") (pintype "passive"))
      (node (ref "JP130") (pin "6") (pinfunction "6_6") (pintype "passive"))
      (node (ref "JP130") (pin "7") (pinfunction "7_7") (pintype "passive"))
      (node (ref "JP130") (pin "8") (pinfunction "8_8") (pintype "passive"))
      (node (ref "JP130") (pin "9") (pinfunction "9_9") (pintype "passive"))
      (node (ref "JP131") (pin "1") (pinfunction "1_1") (pintype "passive"))
      (node (ref "JP131") (pin "2") (pinfunction "2_2") (pintype "passive"))
      (node (ref "JP131") (pin "3") (pinfunction "3_3") (pintype "passive"))
      (node (ref "JP131") (pin "4") (pinfunction "4_4") (pintype "passive"))
      (node (ref "JP131") (pin "5") (pinfunction "5_5") (pintype "passive"))
      (node (ref "JP146") (pin "2") (pinfunction "2_2") (pintype "passive"))
      (node (ref "JP148") (pin "2") (pinfunction "2_2") (pintype "passive"))
      (node (ref "JP2") (pin "1") (pinfunction "1_1") (pintype "passive"))
      (node (ref "JP2") (pin "10") (pinfunction "10_10") (pintype "passive"))
      (node (ref "JP2") (pin "11") (pinfunction "11_11") (pintype "passive"))
      (node (ref "JP2") (pin "12") (pinfunction "12_12") (pintype "passive"))
      (node (ref "JP2") (pin "13") (pinfunction "13_13") (pintype "passive"))
      (node (ref "JP2") (pin "14") (pinfunction "14_14") (pintype "passive"))
      (node (ref "JP2") (pin "15") (pinfunction "15_15") (pintype "passive"))
      (node (ref "JP2") (pin "16") (pinfunction "16_16") (pintype "passive"))
      (node (ref "JP2") (pin "17") (pinfunction "17_17") (pintype "passive"))
      (node (ref "JP2") (pin "18") (pinfunction "18_18") (pintype "passive"))
      (node (ref "JP2") (pin "19") (pinfunction "19_19") (pintype "passive"))
      (node (ref "JP2") (pin "2") (pinfunction "2_2") (pintype "passive"))
      (node (ref "JP2") (pin "20") (pinfunction "20_20") (pintype "passive"))
      (node (ref "JP2") (pin "21") (pinfunction "21_21") (pintype "passive"))
      (node (ref "JP2") (pin "22") (pinfunction "22_22") (pintype "passive"))
      (node (ref "JP2") (pin "23") (pinfunction "23_23") (pintype "passive"))
      (node (ref "JP2") (pin "24") (pinfunction "24_24") (pintype "passive"))
      (node (ref "JP2") (pin "25") (pinfunction "25_25") (pintype "passive"))
      (node (ref "JP2") (pin "26") (pinfunction "26_26") (pintype "passive"))
      (node (ref "JP2") (pin "27") (pinfunction "27_27") (pintype "passive"))
      (node (ref "JP2") (pin "28") (pinfunction "28_28") (pintype "passive"))
      (node (ref "JP2") (pin "29") (pinfunction "29_29") (pintype "passive"))
      (node (ref "JP2") (pin "3") (pinfunction "3_3") (pintype "passive"))
      (node (ref "JP2") (pin "4") (pinfunction "4_4") (pintype "passive"))
      (node (ref "JP2") (pin "5") (pinfunction "5_5") (pintype "passive"))
      (node (ref "JP2") (pin "6") (pinfunction "6_6") (pintype "passive"))
      (node (ref "JP2") (pin "7") (pinfunction "7_7") (pintype "passive"))
      (node (ref "JP2") (pin "8") (pinfunction "8_8") (pintype "passive"))
      (node (ref "JP2") (pin "9") (pinfunction "9_9") (pintype "passive"))
    )
    (net (code "123") (name "Net-(JP133-Pad1)") (class "Default")
      (node (ref "JP133") (pin "1") (pinfunction "1_1") (pintype "passive"))
      (node (ref "JP133") (pin "10") (pinfunction "10_10") (pintype "passive"))
      (node (ref "JP133") (pin "11") (pinfunction "11_11") (pintype "passive"))
      (node (ref "JP133") (pin "12") (pinfunction "12_12") (pintype "passive"))
      (node (ref "JP133") (pin "13") (pinfunction "13_13") (pintype "passive"))
      (node (ref "JP133") (pin "14") (pinfunction "14_14") (pintype "passive"))
      (node (ref "JP133") (pin "15") (pinfunction "15_15") (pintype "passive"))
      (node (ref "JP133") (pin "16") (pinfunction "16_16") (pintype "passive"))
      (node (ref "JP133") (pin "17") (pinfunction "17_17") (pintype "passive"))
      (node (ref "JP133") (pin "18") (pinfunction "18_18") (pintype "passive"))
      (node (ref "JP133") (pin "19") (pinfunction "19_19") (pintype "passive"))
      (node (ref "JP133") (pin "2") (pinfunction "2_2") (pintype "passive"))
      (node (ref "JP133") (pin "20") (pinfunction "20_20") (pintype "passive"))
      (node (ref "JP133") (pin "21") (pinfunction "21_21") (pintype "passive"))
      (node (ref "JP133") (pin "22") (pinfunction "22_22") (pintype "passive"))
      (node (ref "JP133") (pin "23") (pinfunction "23_23") (pintype "passive"))
      (node (ref "JP133") (pin "24") (pinfunction "24_24") (pintype "passive"))
      (node (ref "JP133") (pin "25") (pinfunction "25_25") (pintype "passive"))
      (node (ref "JP133") (pin "26") (pinfunction "26_26") (pintype "passive"))
      (node (ref "JP133") (pin "27") (pinfunction "27_27") (pintype "passive"))
      (node (ref "JP133") (pin "28") (pinfunction "28_28") (pintype "passive"))
      (node (ref "JP133") (pin "29") (pinfunction "29_29") (pintype "passive"))
      (node (ref "JP133") (pin "3") (pinfunction "3_3") (pintype "passive"))
      (node (ref "JP133") (pin "4") (pinfunction "4_4") (pintype "passive"))
      (node (ref "JP133") (pin "5") (pinfunction "5_5") (pintype "passive"))
      (node (ref "JP133") (pin "6") (pinfunction "6_6") (pintype "passive"))
      (node (ref "JP133") (pin "7") (pinfunction "7_7") (pintype "passive"))
      (node (ref "JP133") (pin "8") (pinfunction "8_8") (pintype "passive"))
      (node (ref "JP133") (pin "9") (pinfunction "9_9") (pintype "passive"))
      (node (ref "JP136") (pin "1") (pinfunction "1_1") (pintype "passive"))
      (node (ref "JP136") (pin "2") (pinfunction "2_2") (pintype "passive"))
      (node (ref "JP136") (pin "3") (pinfunction "3_3") (pintype "passive"))
      (node (ref "JP136") (pin "4") (pinfunction "4_4") (pintype "passive"))
      (node (ref "JP136") (pin "5") (pinfunction "5_5") (pintype "passive"))
      (node (ref "JP147") (pin "2") (pinfunction "2_2") (pintype "passive"))
      (node (ref "JP149") (pin "2") (pinfunction "2_2") (pintype "passive"))
      (node (ref "JP3") (pin "1") (pinfunction "1_1") (pintype "passive"))
      (node (ref "JP3") (pin "10") (pinfunction "10_10") (pintype "passive"))
      (node (ref "JP3") (pin "11") (pinfunction "11_11") (pintype "passive"))
      (node (ref "JP3") (pin "12") (pinfunction "12_12") (pintype "passive"))
      (node (ref "JP3") (pin "13") (pinfunction "13_13") (pintype "passive"))
      (node (ref "JP3") (pin "14") (pinfunction "14_14") (pintype "passive"))
      (node (ref "JP3") (pin "15") (pinfunction "15_15") (pintype "passive"))
      (node (ref "JP3") (pin "16") (pinfunction "16_16") (pintype "passive"))
      (node (ref "JP3") (pin "17") (pinfunction "17_17") (pintype "passive"))
      (node (ref "JP3") (pin "18") (pinfunction "18_18") (pintype "passive"))
      (node (ref "JP3") (pin "19") (pinfunction "19_19") (pintype "passive"))
      (node (ref "JP3") (pin "2") (pinfunction "2_2") (pintype "passive"))
      (node (ref "JP3") (pin "20") (pinfunction "20_20") (pintype "passive"))
      (node (ref "JP3") (pin "21") (pinfunction "21_21") (pintype "passive"))
      (node (ref "JP3") (pin "22") (pinfunction "22_22") (pintype "passive"))
      (node (ref "JP3") (pin "23") (pinfunction "23_23") (pintype "passive"))
      (node (ref "JP3") (pin "24") (pinfunction "24_24") (pintype "passive"))
      (node (ref "JP3") (pin "25") (pinfunction "25_25") (pintype "passive"))
      (node (ref "JP3") (pin "26") (pinfunction "26_26") (pintype "passive"))
      (node (ref "JP3") (pin "27") (pinfunction "27_27") (pintype "passive"))
      (node (ref "JP3") (pin "28") (pinfunction "28_28") (pintype "passive"))
      (node (ref "JP3") (pin "29") (pinfunction "29_29") (pintype "passive"))
      (node (ref "JP3") (pin "3") (pinfunction "3_3") (pintype "passive"))
      (node (ref "JP3") (pin "4") (pinfunction "4_4") (pintype "passive"))
      (node (ref "JP3") (pin "5") (pinfunction "5_5") (pintype "passive"))
      (node (ref "JP3") (pin "6") (pinfunction "6_6") (pintype "passive"))
      (node (ref "JP3") (pin "7") (pinfunction "7_7") (pintype "passive"))
      (node (ref "JP3") (pin "8") (pinfunction "8_8") (pintype "passive"))
      (node (ref "JP3") (pin "9") (pinfunction "9_9") (pintype "passive"))
    )
    (net (code "124") (name "Net-(JP134-Pad1)") (class "Default")
      (node (ref "JP134") (pin "1") (pinfunction "1_1") (pintype "passive"))
      (node (ref "JP134") (pin "10") (pinfunction "10_10") (pintype "passive"))
      (node (ref "JP134") (pin "11") (pinfunction "11_11") (pintype "passive"))
      (node (ref "JP134") (pin "12") (pinfunction "12_12") (pintype "passive"))
      (node (ref "JP134") (pin "13") (pinfunction "13_13") (pintype "passive"))
      (node (ref "JP134") (pin "14") (pinfunction "14_14") (pintype "passive"))
      (node (ref "JP134") (pin "15") (pinfunction "15_15") (pintype "passive"))
      (node (ref "JP134") (pin "16") (pinfunction "16_16") (pintype "passive"))
      (node (ref "JP134") (pin "17") (pinfunction "17_17") (pintype "passive"))
      (node (ref "JP134") (pin "18") (pinfunction "18_18") (pintype "passive"))
      (node (ref "JP134") (pin "19") (pinfunction "19_19") (pintype "passive"))
      (node (ref "JP134") (pin "2") (pinfunction "2_2") (pintype "passive"))
      (node (ref "JP134") (pin "20") (pinfunction "20_20") (pintype "passive"))
      (node (ref "JP134") (pin "21") (pinfunction "21_21") (pintype "passive"))
      (node (ref "JP134") (pin "22") (pinfunction "22_22") (pintype "passive"))
      (node (ref "JP134") (pin "23") (pinfunction "23_23") (pintype "passive"))
      (node (ref "JP134") (pin "24") (pinfunction "24_24") (pintype "passive"))
      (node (ref "JP134") (pin "25") (pinfunction "25_25") (pintype "passive"))
      (node (ref "JP134") (pin "26") (pinfunction "26_26") (pintype "passive"))
      (node (ref "JP134") (pin "27") (pinfunction "27_27") (pintype "passive"))
      (node (ref "JP134") (pin "28") (pinfunction "28_28") (pintype "passive"))
      (node (ref "JP134") (pin "29") (pinfunction "29_29") (pintype "passive"))
      (node (ref "JP134") (pin "3") (pinfunction "3_3") (pintype "passive"))
      (node (ref "JP134") (pin "4") (pinfunction "4_4") (pintype "passive"))
      (node (ref "JP134") (pin "5") (pinfunction "5_5") (pintype "passive"))
      (node (ref "JP134") (pin "6") (pinfunction "6_6") (pintype "passive"))
      (node (ref "JP134") (pin "7") (pinfunction "7_7") (pintype "passive"))
      (node (ref "JP134") (pin "8") (pinfunction "8_8") (pintype "passive"))
      (node (ref "JP134") (pin "9") (pinfunction "9_9") (pintype "passive"))
      (node (ref "JP135") (pin "1") (pinfunction "1_1") (pintype "passive"))
      (node (ref "JP135") (pin "2") (pinfunction "2_2") (pintype "passive"))
      (node (ref "JP135") (pin "3") (pinfunction "3_3") (pintype "passive"))
      (node (ref "JP135") (pin "4") (pinfunction "4_4") (pintype "passive"))
      (node (ref "JP135") (pin "5") (pinfunction "5_5") (pintype "passive"))
      (node (ref "JP147") (pin "3") (pinfunction "3_3") (pintype "passive"))
      (node (ref "JP149") (pin "1") (pinfunction "1_1") (pintype "passive"))
      (node (ref "JP4") (pin "1") (pinfunction "1_1") (pintype "passive"))
      (node (ref "JP4") (pin "10") (pinfunction "10_10") (pintype "passive"))
      (node (ref "JP4") (pin "11") (pinfunction "11_11") (pintype "passive"))
      (node (ref "JP4") (pin "12") (pinfunction "12_12") (pintype "passive"))
      (node (ref "JP4") (pin "13") (pinfunction "13_13") (pintype "passive"))
      (node (ref "JP4") (pin "14") (pinfunction "14_14") (pintype "passive"))
      (node (ref "JP4") (pin "15") (pinfunction "15_15") (pintype "passive"))
      (node (ref "JP4") (pin "16") (pinfunction "16_16") (pintype "passive"))
      (node (ref "JP4") (pin "17") (pinfunction "17_17") (pintype "passive"))
      (node (ref "JP4") (pin "18") (pinfunction "18_18") (pintype "passive"))
      (node (ref "JP4") (pin "19") (pinfunction "19_19") (pintype "passive"))
      (node (ref "JP4") (pin "2") (pinfunction "2_2") (pintype "passive"))
      (node (ref "JP4") (pin "20") (pinfunction "20_20") (pintype "passive"))
      (node (ref "JP4") (pin "21") (pinfunction "21_21") (pintype "passive"))
      (node (ref "JP4") (pin "22") (pinfunction "22_22") (pintype "passive"))
      (node (ref "JP4") (pin "23") (pinfunction "23_23") (pintype "passive"))
      (node (ref "JP4") (pin "24") (pinfunction "24_24") (pintype "passive"))
      (node (ref "JP4") (pin "25") (pinfunction "25_25") (pintype "passive"))
      (node (ref "JP4") (pin "26") (pinfunction "26_26") (pintype "passive"))
      (node (ref "JP4") (pin "27") (pinfunction "27_27") (pintype "passive"))
      (node (ref "JP4") (pin "28") (pinfunction "28_28") (pintype "passive"))
      (node (ref "JP4") (pin "29") (pinfunction "29_29") (pintype "passive"))
      (node (ref "JP4") (pin "3") (pinfunction "3_3") (pintype "passive"))
      (node (ref "JP4") (pin "4") (pinfunction "4_4") (pintype "passive"))
      (node (ref "JP4") (pin "5") (pinfunction "5_5") (pintype "passive"))
      (node (ref "JP4") (pin "6") (pinfunction "6_6") (pintype "passive"))
      (node (ref "JP4") (pin "7") (pinfunction "7_7") (pintype "passive"))
      (node (ref "JP4") (pin "8") (pinfunction "8_8") (pintype "passive"))
      (node (ref "JP4") (pin "9") (pinfunction "9_9") (pintype "passive"))
    )
    (net (code "125") (name "Net-(JP137-Pad1)") (class "Default")
      (node (ref "JP137") (pin "1") (pinfunction "1_1") (pintype "passive"))
      (node (ref "JP137") (pin "10") (pinfunction "10_10") (pintype "passive"))
      (node (ref "JP137") (pin "11") (pinfunction "11_11") (pintype "passive"))
      (node (ref "JP137") (pin "12") (pinfunction "12_12") (pintype "passive"))
      (node (ref "JP137") (pin "13") (pinfunction "13_13") (pintype "passive"))
      (node (ref "JP137") (pin "14") (pinfunction "14_14") (pintype "passive"))
      (node (ref "JP137") (pin "15") (pinfunction "15_15") (pintype "passive"))
      (node (ref "JP137") (pin "16") (pinfunction "16_16") (pintype "passive"))
      (node (ref "JP137") (pin "17") (pinfunction "17_17") (pintype "passive"))
      (node (ref "JP137") (pin "18") (pinfunction "18_18") (pintype "passive"))
      (node (ref "JP137") (pin "19") (pinfunction "19_19") (pintype "passive"))
      (node (ref "JP137") (pin "2") (pinfunction "2_2") (pintype "passive"))
      (node (ref "JP137") (pin "20") (pinfunction "20_20") (pintype "passive"))
      (node (ref "JP137") (pin "21") (pinfunction "21_21") (pintype "passive"))
      (node (ref "JP137") (pin "22") (pinfunction "22_22") (pintype "passive"))
      (node (ref "JP137") (pin "23") (pinfunction "23_23") (pintype "passive"))
      (node (ref "JP137") (pin "24") (pinfunction "24_24") (pintype "passive"))
      (node (ref "JP137") (pin "25") (pinfunction "25_25") (pintype "passive"))
      (node (ref "JP137") (pin "26") (pinfunction "26_26") (pintype "passive"))
      (node (ref "JP137") (pin "27") (pinfunction "27_27") (pintype "passive"))
      (node (ref "JP137") (pin "28") (pinfunction "28_28") (pintype "passive"))
      (node (ref "JP137") (pin "29") (pinfunction "29_29") (pintype "passive"))
      (node (ref "JP137") (pin "3") (pinfunction "3_3") (pintype "passive"))
      (node (ref "JP137") (pin "4") (pinfunction "4_4") (pintype "passive"))
      (node (ref "JP137") (pin "5") (pinfunction "5_5") (pintype "passive"))
      (node (ref "JP137") (pin "6") (pinfunction "6_6") (pintype "passive"))
      (node (ref "JP137") (pin "7") (pinfunction "7_7") (pintype "passive"))
      (node (ref "JP137") (pin "8") (pinfunction "8_8") (pintype "passive"))
      (node (ref "JP137") (pin "9") (pinfunction "9_9") (pintype "passive"))
      (node (ref "JP138") (pin "1") (pinfunction "1_1") (pintype "passive"))
      (node (ref "JP138") (pin "10") (pinfunction "10_10") (pintype "passive"))
      (node (ref "JP138") (pin "11") (pinfunction "11_11") (pintype "passive"))
      (node (ref "JP138") (pin "12") (pinfunction "12_12") (pintype "passive"))
      (node (ref "JP138") (pin "13") (pinfunction "13_13") (pintype "passive"))
      (node (ref "JP138") (pin "14") (pinfunction "14_14") (pintype "passive"))
      (node (ref "JP138") (pin "15") (pinfunction "15_15") (pintype "passive"))
      (node (ref "JP138") (pin "16") (pinfunction "16_16") (pintype "passive"))
      (node (ref "JP138") (pin "17") (pinfunction "17_17") (pintype "passive"))
      (node (ref "JP138") (pin "18") (pinfunction "18_18") (pintype "passive"))
      (node (ref "JP138") (pin "19") (pinfunction "19_19") (pintype "passive"))
      (node (ref "JP138") (pin "2") (pinfunction "2_2") (pintype "passive"))
      (node (ref "JP138") (pin "20") (pinfunction "20_20") (pintype "passive"))
      (node (ref "JP138") (pin "21") (pinfunction "21_21") (pintype "passive"))
      (node (ref "JP138") (pin "22") (pinfunction "22_22") (pintype "passive"))
      (node (ref "JP138") (pin "23") (pinfunction "23_23") (pintype "passive"))
      (node (ref "JP138") (pin "24") (pinfunction "24_24") (pintype "passive"))
      (node (ref "JP138") (pin "25") (pinfunction "25_25") (pintype "passive"))
      (node (ref "JP138") (pin "26") (pinfunction "26_26") (pintype "passive"))
      (node (ref "JP138") (pin "27") (pinfunction "27_27") (pintype "passive"))
      (node (ref "JP138") (pin "28") (pinfunction "28_28") (pintype "passive"))
      (node (ref "JP138") (pin "29") (pinfunction "29_29") (pintype "passive"))
      (node (ref "JP138") (pin "3") (pinfunction "3_3") (pintype "passive"))
      (node (ref "JP138") (pin "4") (pinfunction "4_4") (pintype "passive"))
      (node (ref "JP138") (pin "5") (pinfunction "5_5") (pintype "passive"))
      (node (ref "JP138") (pin "6") (pinfunction "6_6") (pintype "passive"))
      (node (ref "JP138") (pin "7") (pinfunction "7_7") (pintype "passive"))
      (node (ref "JP138") (pin "8") (pinfunction "8_8") (pintype "passive"))
      (node (ref "JP138") (pin "9") (pinfunction "9_9") (pintype "passive"))
      (node (ref "JP139") (pin "1") (pinfunction "1_1") (pintype "passive"))
      (node (ref "JP139") (pin "2") (pinfunction "2_2") (pintype "passive"))
      (node (ref "JP139") (pin "3") (pinfunction "3_3") (pintype "passive"))
      (node (ref "JP139") (pin "4") (pinfunction "4_4") (pintype "passive"))
      (node (ref "JP139") (pin "5") (pinfunction "5_5") (pintype "passive"))
      (node (ref "JP146") (pin "1") (pinfunction "1_1") (pintype "passive"))
      (node (ref "JP147") (pin "1") (pinfunction "1_1") (pintype "passive"))
      (node (ref "JP150") (pin "1") (pinfunction "1_1") (pintype "passive"))
      (node (ref "JP151") (pin "1") (pinfunction "1_1") (pintype "passive"))
      (node (ref "JP152") (pin "1") (pinfunction "1_1") (pintype "passive"))
      (node (ref "JP153") (pin "1") (pinfunction "1_1") (pintype "passive"))
    )
    (net (code "126") (name "Net-(JP140-Pad1)") (class "Default")
      (node (ref "JP140") (pin "1") (pinfunction "1_1") (pintype "passive"))
      (node (ref "JP140") (pin "2") (pinfunction "2_2") (pintype "passive"))
      (node (ref "JP140") (pin "3") (pinfunction "3_3") (pintype "passive"))
      (node (ref "JP140") (pin "4") (pinfunction "4_4") (pintype "passive"))
      (node (ref "JP140") (pin "5") (pinfunction "5_5") (pintype "passive"))
    )
    (net (code "127") (name "Net-(JP141-Pad1)") (class "Default")
      (node (ref "JP141") (pin "1") (pinfunction "1_1") (pintype "passive"))
      (node (ref "JP141") (pin "2") (pinfunction "2_2") (pintype "passive"))
      (node (ref "JP141") (pin "3") (pinfunction "3_3") (pintype "passive"))
      (node (ref "JP141") (pin "4") (pinfunction "4_4") (pintype "passive"))
      (node (ref "JP141") (pin "5") (pinfunction "5_5") (pintype "passive"))
    )
    (net (code "128") (name "Net-(JP142-Pad1)") (class "Default")
      (node (ref "JP142") (pin "1") (pinfunction "1_1") (pintype "passive"))
      (node (ref "JP142") (pin "2") (pinfunction "2_2") (pintype "passive"))
      (node (ref "JP142") (pin "3") (pinfunction "3_3") (pintype "passive"))
      (node (ref "JP142") (pin "4") (pinfunction "4_4") (pintype "passive"))
      (node (ref "JP142") (pin "5") (pinfunction "5_5") (pintype "passive"))
    )
    (net (code "129") (name "Net-(JP143-Pad1)") (class "Default")
      (node (ref "JP143") (pin "1") (pinfunction "1_1") (pintype "passive"))
      (node (ref "JP143") (pin "2") (pinfunction "2_2") (pintype "passive"))
      (node (ref "JP143") (pin "3") (pinfunction "3_3") (pintype "passive"))
      (node (ref "JP143") (pin "4") (pinfunction "4_4") (pintype "passive"))
      (node (ref "JP143") (pin "5") (pinfunction "5_5") (pintype "passive"))
    )
    (net (code "130") (name "Net-(JP144-Pad1)") (class "Default")
      (node (ref "JP144") (pin "1") (pinfunction "1_1") (pintype "passive"))
      (node (ref "JP144") (pin "2") (pinfunction "2_2") (pintype "passive"))
      (node (ref "JP144") (pin "3") (pinfunction "3_3") (pintype "passive"))
      (node (ref "JP144") (pin "4") (pinfunction "4_4") (pintype "passive"))
      (node (ref "JP144") (pin "5") (pinfunction "5_5") (pintype "passive"))
    )
    (net (code "131") (name "Net-(JP145-Pad1)") (class "Default")
      (node (ref "JP145") (pin "1") (pinfunction "1_1") (pintype "passive"))
      (node (ref "JP145") (pin "2") (pinfunction "2_2") (pintype "passive"))
      (node (ref "JP145") (pin "3") (pinfunction "3_3") (pintype "passive"))
      (node (ref "JP145") (pin "4") (pinfunction "4_4") (pintype "passive"))
      (node (ref "JP145") (pin "5") (pinfunction "5_5") (pintype "passive"))
    )
    (net (code "132") (name "Net-(S1-P$1)") (class "Default")
      (node (ref "JP66") (pin "1") (pinfunction "1_1") (pintype "passive"))
      (node (ref "S1") (pin "P1") (pinfunction "P$1_P1") (pintype "bidirectional"))
    )
    (net (code "133") (name "Net-(S2-P$1)") (class "Default")
      (node (ref "JP65") (pin "1") (pinfunction "1_1") (pintype "passive"))
      (node (ref "S2") (pin "P1") (pinfunction "P$1_P1") (pintype "bidirectional"))
    )
    (net (code "134") (name "Net-(S3-P$1)") (class "Default")
      (node (ref "JP67") (pin "1") (pinfunction "1_1") (pintype "passive"))
      (node (ref "S3") (pin "P1") (pinfunction "P$1_P1") (pintype "bidirectional"))
    )
    (net (code "135") (name "Net-(S4-P$1)") (class "Default")
      (node (ref "JP68") (pin "1") (pinfunction "1_1") (pintype "passive"))
      (node (ref "S4") (pin "P1") (pinfunction "P$1_P1") (pintype "bidirectional"))
    )
  )
)
